# usb_keyboard.net
KiCad netlist of a schematic drawn in Altium Designer
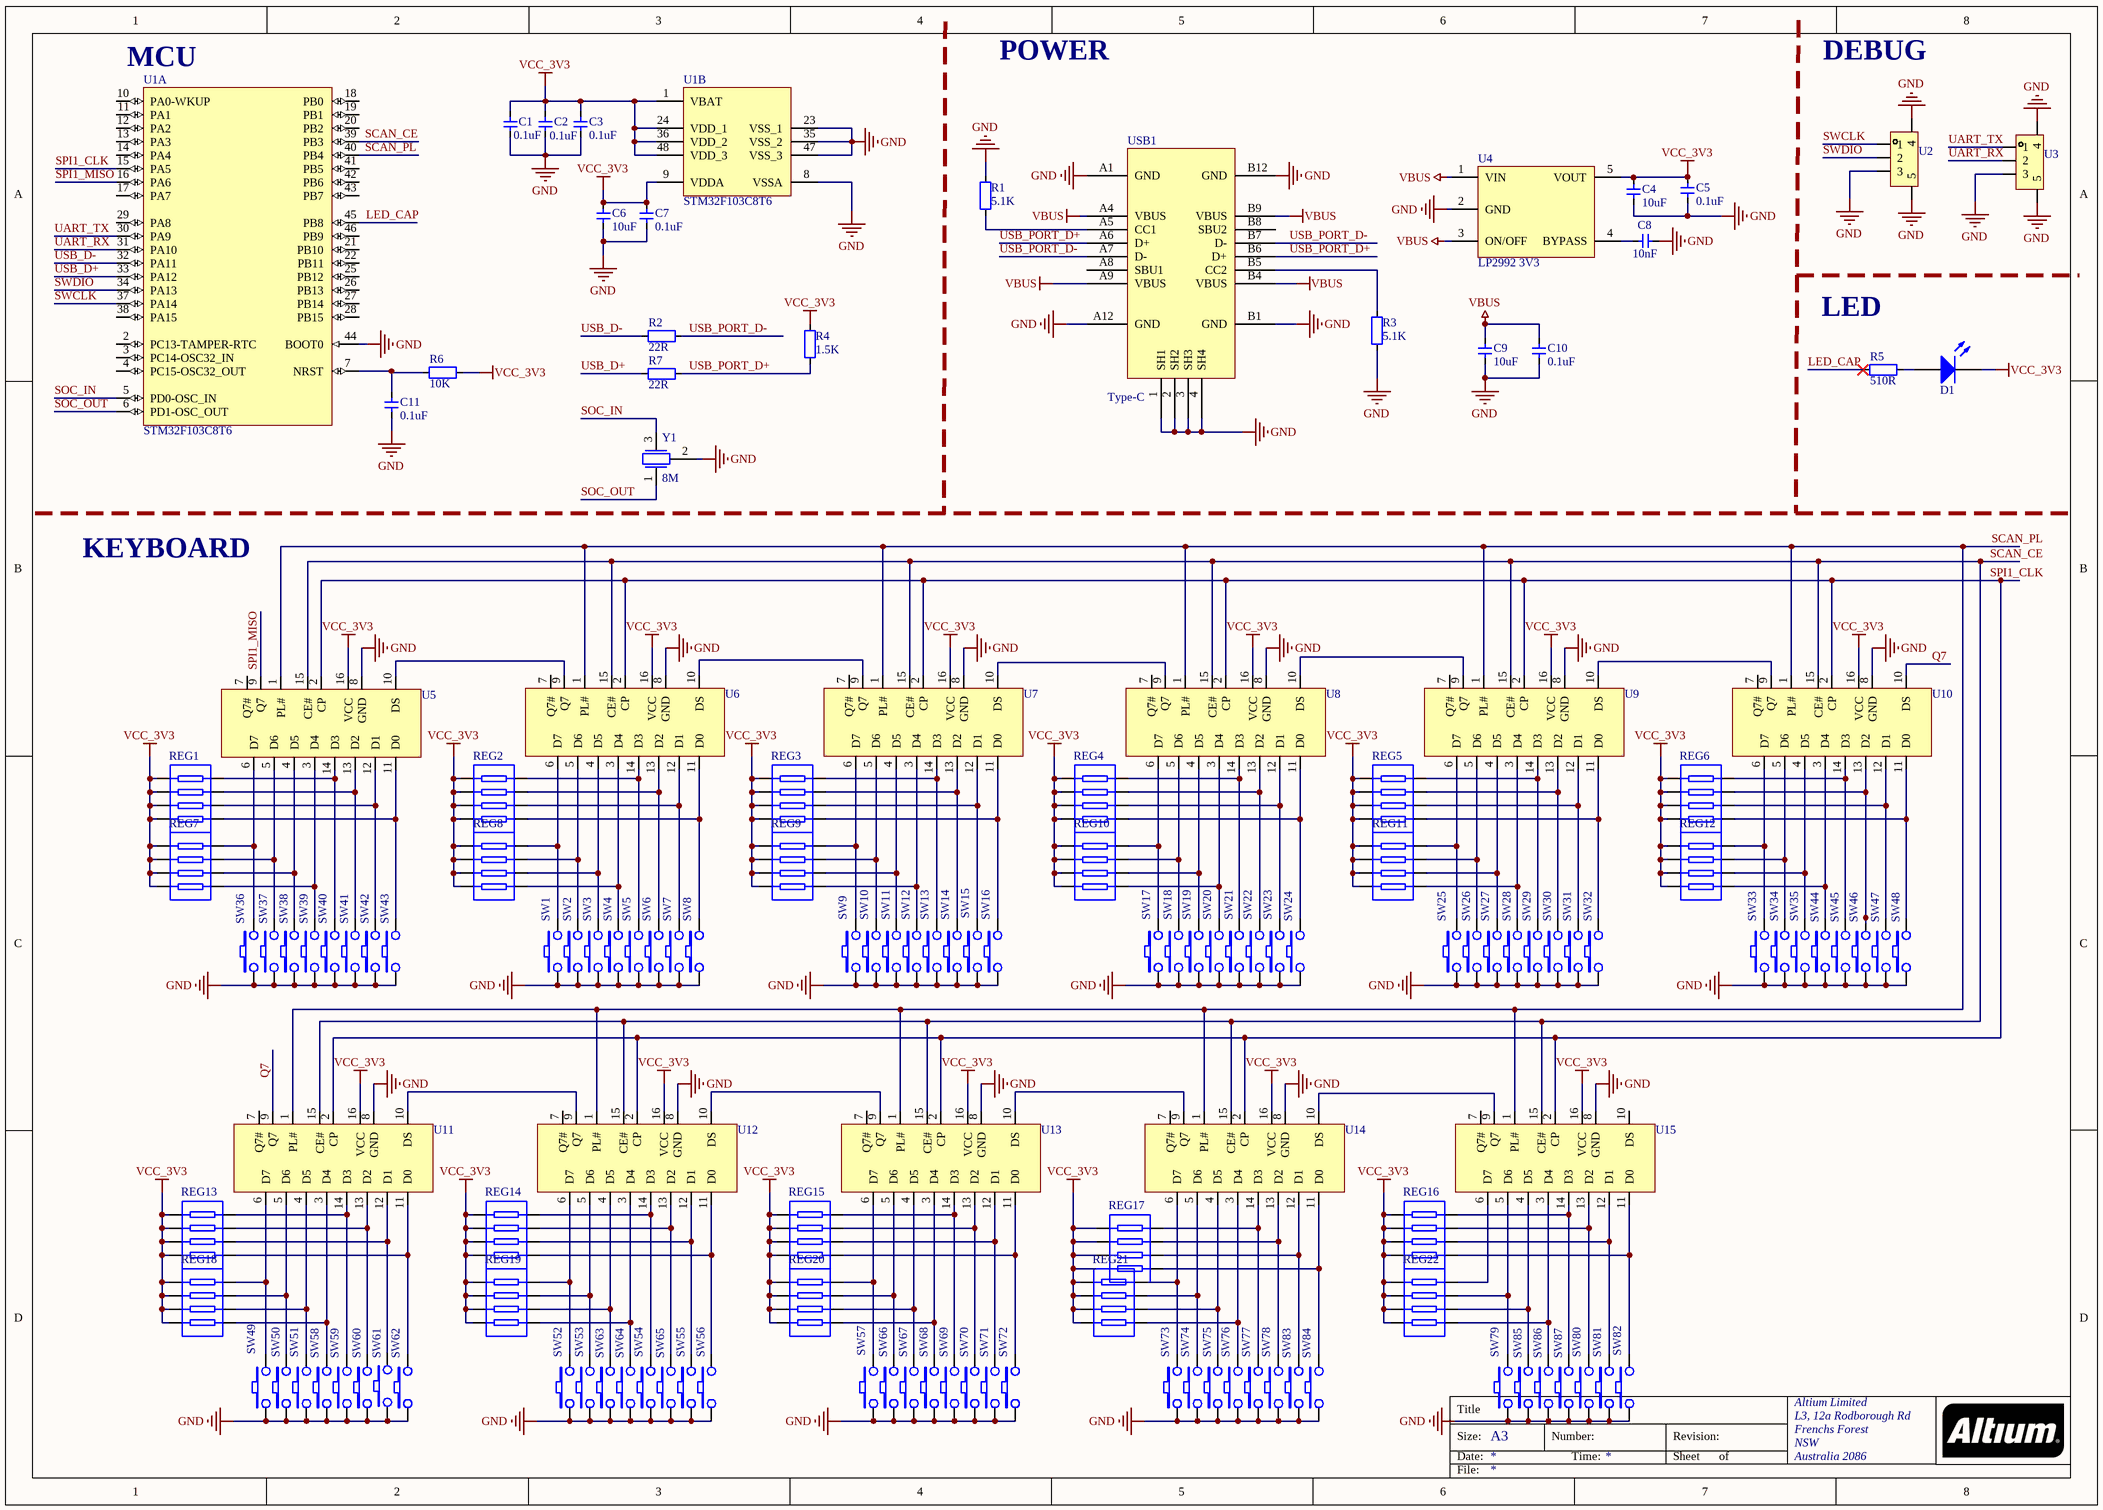
[diagram p0: usb_keyboard.SchDoc]

(export (version "E")
  (design (tool "Eeschema 10.0.6"))
  (components
    (comp (ref "C1")
      (value "0.1uF")
      (footprint "CAP_0603")
      (description "Capacitor")
      (libsource (lib "Integrated_Library") (part "电容"))
    )
    (comp (ref "C2")
      (value "0.1uF")
      (footprint "CAP_0603")
      (description "Capacitor")
      (libsource (lib "Integrated_Library") (part "电容"))
    )
    (comp (ref "C3")
      (value "0.1uF")
      (footprint "CAP_0603")
      (description "Capacitor")
      (libsource (lib "Integrated_Library") (part "电容"))
    )
    (comp (ref "C4")
      (value "10uF")
      (footprint "CAP_0603")
      (description "Capacitor")
      (libsource (lib "Integrated_Library") (part "电容"))
    )
    (comp (ref "C5")
      (value "0.1uF")
      (footprint "CAP_0603")
      (description "Capacitor")
      (libsource (lib "Integrated_Library") (part "电容"))
    )
    (comp (ref "C6")
      (value "10uF")
      (footprint "CAP_0603")
      (description "Capacitor")
      (libsource (lib "Integrated_Library") (part "电容"))
    )
    (comp (ref "C7")
      (value "0.1uF")
      (footprint "CAP_0603")
      (description "Capacitor")
      (libsource (lib "Integrated_Library") (part "电容"))
    )
    (comp (ref "C8")
      (value "10nF")
      (footprint "CAP_0603")
      (description "Capacitor")
      (libsource (lib "Integrated_Library") (part "电容"))
    )
    (comp (ref "C9")
      (value "10uF")
      (footprint "CAP_0603")
      (description "Capacitor")
      (libsource (lib "Integrated_Library") (part "电容"))
    )
    (comp (ref "C10")
      (value "0.1uF")
      (footprint "CAP_0603")
      (description "Capacitor")
      (libsource (lib "Integrated_Library") (part "电容"))
    )
    (comp (ref "C11")
      (value "0.1uF")
      (footprint "CAP_0603")
      (description "Capacitor")
      (libsource (lib "Integrated_Library") (part "电容"))
    )
    (comp (ref "D1")
      (value "LED")
      (footprint "LED_0603")
      (description "Typical INFRARED GaAs LED")
      (fields (field (name "PUBLISHER") "Altium Limited"))
      (libsource (lib "Integrated_Library") (part "LED"))
    )
    (comp (ref "R1")
      (value "5.1K")
      (footprint "REG_0603")
      (description "Resistor")
      (libsource (lib "") (part "电阻_1"))
    )
    (comp (ref "R2")
      (value "22R")
      (footprint "REG_0603")
      (description "Resistor")
      (libsource (lib "Integrated_Library") (part "电阻"))
    )
    (comp (ref "R3")
      (value "5.1K")
      (footprint "REG_0603")
      (description "Resistor")
      (libsource (lib "") (part "电阻_1"))
    )
    (comp (ref "R4")
      (value "1.5K")
      (footprint "REG_0603")
      (description "Resistor")
      (libsource (lib "") (part "电阻_1"))
    )
    (comp (ref "R5")
      (value "510R")
      (footprint "REG_0603")
      (description "Resistor")
      (libsource (lib "Integrated_Library") (part "电阻"))
    )
    (comp (ref "R6")
      (value "10K")
      (footprint "REG_0603")
      (description "Resistor")
      (libsource (lib "Integrated_Library") (part "电阻"))
    )
    (comp (ref "R7")
      (value "22R")
      (footprint "REG_0603")
      (description "Resistor")
      (libsource (lib "Integrated_Library") (part "电阻"))
    )
    (comp (ref "REG1")
      (value "4D03WGJ0103T5E")
      (footprint "RES-ARRAY-SMD_0603-8P-L3.2-W1.6-BL")
      (description "阻值:10kΩ;精度:±5%;单个元件功率:62.5mW;温度系数:±200ppm/;电阻器数:4;引脚数:8;")
      (fields (field (name "MANUFACTURER") "UNI-ROYAL(厚声)") (field (name "TOLERANCE") "±5%"))
      (libsource (lib "Integrated_Library") (part "排阻"))
    )
    (comp (ref "REG2")
      (value "4D03WGJ0103T5E")
      (footprint "RES-ARRAY-SMD_0603-8P-L3.2-W1.6-BL")
      (description "阻值:10kΩ;精度:±5%;单个元件功率:62.5mW;温度系数:±200ppm/;电阻器数:4;引脚数:8;")
      (fields (field (name "MANUFACTURER") "UNI-ROYAL(厚声)") (field (name "TOLERANCE") "±5%"))
      (libsource (lib "Integrated_Library") (part "排阻"))
    )
    (comp (ref "REG3")
      (value "4D03WGJ0103T5E")
      (footprint "RES-ARRAY-SMD_0603-8P-L3.2-W1.6-BL")
      (description "阻值:10kΩ;精度:±5%;单个元件功率:62.5mW;温度系数:±200ppm/;电阻器数:4;引脚数:8;")
      (fields (field (name "MANUFACTURER") "UNI-ROYAL(厚声)") (field (name "TOLERANCE") "±5%"))
      (libsource (lib "Integrated_Library") (part "排阻"))
    )
    (comp (ref "REG4")
      (value "4D03WGJ0103T5E")
      (footprint "RES-ARRAY-SMD_0603-8P-L3.2-W1.6-BL")
      (description "阻值:10kΩ;精度:±5%;单个元件功率:62.5mW;温度系数:±200ppm/;电阻器数:4;引脚数:8;")
      (fields (field (name "MANUFACTURER") "UNI-ROYAL(厚声)") (field (name "TOLERANCE") "±5%"))
      (libsource (lib "Integrated_Library") (part "排阻"))
    )
    (comp (ref "REG5")
      (value "4D03WGJ0103T5E")
      (footprint "RES-ARRAY-SMD_0603-8P-L3.2-W1.6-BL")
      (description "阻值:10kΩ;精度:±5%;单个元件功率:62.5mW;温度系数:±200ppm/;电阻器数:4;引脚数:8;")
      (fields (field (name "MANUFACTURER") "UNI-ROYAL(厚声)") (field (name "TOLERANCE") "±5%"))
      (libsource (lib "Integrated_Library") (part "排阻"))
    )
    (comp (ref "REG6")
      (value "4D03WGJ0103T5E")
      (footprint "RES-ARRAY-SMD_0603-8P-L3.2-W1.6-BL")
      (description "阻值:10kΩ;精度:±5%;单个元件功率:62.5mW;温度系数:±200ppm/;电阻器数:4;引脚数:8;")
      (fields (field (name "MANUFACTURER") "UNI-ROYAL(厚声)") (field (name "TOLERANCE") "±5%"))
      (libsource (lib "Integrated_Library") (part "排阻"))
    )
    (comp (ref "REG7")
      (value "4D03WGJ0103T5E")
      (footprint "RES-ARRAY-SMD_0603-8P-L3.2-W1.6-BL")
      (description "阻值:10kΩ;精度:±5%;单个元件功率:62.5mW;温度系数:±200ppm/;电阻器数:4;引脚数:8;")
      (fields (field (name "MANUFACTURER") "UNI-ROYAL(厚声)") (field (name "TOLERANCE") "±5%"))
      (libsource (lib "Integrated_Library") (part "排阻"))
    )
    (comp (ref "REG8")
      (value "4D03WGJ0103T5E")
      (footprint "RES-ARRAY-SMD_0603-8P-L3.2-W1.6-BL")
      (description "阻值:10kΩ;精度:±5%;单个元件功率:62.5mW;温度系数:±200ppm/;电阻器数:4;引脚数:8;")
      (fields (field (name "MANUFACTURER") "UNI-ROYAL(厚声)") (field (name "TOLERANCE") "±5%"))
      (libsource (lib "Integrated_Library") (part "排阻"))
    )
    (comp (ref "REG9")
      (value "4D03WGJ0103T5E")
      (footprint "RES-ARRAY-SMD_0603-8P-L3.2-W1.6-BL")
      (description "阻值:10kΩ;精度:±5%;单个元件功率:62.5mW;温度系数:±200ppm/;电阻器数:4;引脚数:8;")
      (fields (field (name "MANUFACTURER") "UNI-ROYAL(厚声)") (field (name "TOLERANCE") "±5%"))
      (libsource (lib "Integrated_Library") (part "排阻"))
    )
    (comp (ref "REG10")
      (value "4D03WGJ0103T5E")
      (footprint "RES-ARRAY-SMD_0603-8P-L3.2-W1.6-BL")
      (description "阻值:10kΩ;精度:±5%;单个元件功率:62.5mW;温度系数:±200ppm/;电阻器数:4;引脚数:8;")
      (fields (field (name "MANUFACTURER") "UNI-ROYAL(厚声)") (field (name "TOLERANCE") "±5%"))
      (libsource (lib "Integrated_Library") (part "排阻"))
    )
    (comp (ref "REG11")
      (value "4D03WGJ0103T5E")
      (footprint "RES-ARRAY-SMD_0603-8P-L3.2-W1.6-BL")
      (description "阻值:10kΩ;精度:±5%;单个元件功率:62.5mW;温度系数:±200ppm/;电阻器数:4;引脚数:8;")
      (fields (field (name "MANUFACTURER") "UNI-ROYAL(厚声)") (field (name "TOLERANCE") "±5%"))
      (libsource (lib "Integrated_Library") (part "排阻"))
    )
    (comp (ref "REG12")
      (value "4D03WGJ0103T5E")
      (footprint "RES-ARRAY-SMD_0603-8P-L3.2-W1.6-BL")
      (description "阻值:10kΩ;精度:±5%;单个元件功率:62.5mW;温度系数:±200ppm/;电阻器数:4;引脚数:8;")
      (fields (field (name "MANUFACTURER") "UNI-ROYAL(厚声)") (field (name "TOLERANCE") "±5%"))
      (libsource (lib "Integrated_Library") (part "排阻"))
    )
    (comp (ref "REG13")
      (value "4D03WGJ0103T5E")
      (footprint "RES-ARRAY-SMD_0603-8P-L3.2-W1.6-BL")
      (description "阻值:10kΩ;精度:±5%;单个元件功率:62.5mW;温度系数:±200ppm/;电阻器数:4;引脚数:8;")
      (fields (field (name "MANUFACTURER") "UNI-ROYAL(厚声)") (field (name "TOLERANCE") "±5%"))
      (libsource (lib "Integrated_Library") (part "排阻"))
    )
    (comp (ref "REG14")
      (value "4D03WGJ0103T5E")
      (footprint "RES-ARRAY-SMD_0603-8P-L3.2-W1.6-BL")
      (description "阻值:10kΩ;精度:±5%;单个元件功率:62.5mW;温度系数:±200ppm/;电阻器数:4;引脚数:8;")
      (fields (field (name "MANUFACTURER") "UNI-ROYAL(厚声)") (field (name "TOLERANCE") "±5%"))
      (libsource (lib "Integrated_Library") (part "排阻"))
    )
    (comp (ref "REG15")
      (value "4D03WGJ0103T5E")
      (footprint "RES-ARRAY-SMD_0603-8P-L3.2-W1.6-BL")
      (description "阻值:10kΩ;精度:±5%;单个元件功率:62.5mW;温度系数:±200ppm/;电阻器数:4;引脚数:8;")
      (fields (field (name "MANUFACTURER") "UNI-ROYAL(厚声)") (field (name "TOLERANCE") "±5%"))
      (libsource (lib "Integrated_Library") (part "排阻"))
    )
    (comp (ref "REG16")
      (value "4D03WGJ0103T5E")
      (footprint "RES-ARRAY-SMD_0603-8P-L3.2-W1.6-BL")
      (description "阻值:10kΩ;精度:±5%;单个元件功率:62.5mW;温度系数:±200ppm/;电阻器数:4;引脚数:8;")
      (fields (field (name "MANUFACTURER") "UNI-ROYAL(厚声)") (field (name "TOLERANCE") "±5%"))
      (libsource (lib "Integrated_Library") (part "排阻"))
    )
    (comp (ref "REG17")
      (value "4D03WGJ0103T5E")
      (footprint "RES-ARRAY-SMD_0603-8P-L3.2-W1.6-BL")
      (description "阻值:10kΩ;精度:±5%;单个元件功率:62.5mW;温度系数:±200ppm/;电阻器数:4;引脚数:8;")
      (fields (field (name "MANUFACTURER") "UNI-ROYAL(厚声)") (field (name "TOLERANCE") "±5%"))
      (libsource (lib "Integrated_Library") (part "排阻"))
    )
    (comp (ref "REG18")
      (value "4D03WGJ0103T5E")
      (footprint "RES-ARRAY-SMD_0603-8P-L3.2-W1.6-BL")
      (description "阻值:10kΩ;精度:±5%;单个元件功率:62.5mW;温度系数:±200ppm/;电阻器数:4;引脚数:8;")
      (fields (field (name "MANUFACTURER") "UNI-ROYAL(厚声)") (field (name "TOLERANCE") "±5%"))
      (libsource (lib "Integrated_Library") (part "排阻"))
    )
    (comp (ref "REG19")
      (value "4D03WGJ0103T5E")
      (footprint "RES-ARRAY-SMD_0603-8P-L3.2-W1.6-BL")
      (description "阻值:10kΩ;精度:±5%;单个元件功率:62.5mW;温度系数:±200ppm/;电阻器数:4;引脚数:8;")
      (fields (field (name "MANUFACTURER") "UNI-ROYAL(厚声)") (field (name "TOLERANCE") "±5%"))
      (libsource (lib "Integrated_Library") (part "排阻"))
    )
    (comp (ref "REG20")
      (value "4D03WGJ0103T5E")
      (footprint "RES-ARRAY-SMD_0603-8P-L3.2-W1.6-BL")
      (description "阻值:10kΩ;精度:±5%;单个元件功率:62.5mW;温度系数:±200ppm/;电阻器数:4;引脚数:8;")
      (fields (field (name "MANUFACTURER") "UNI-ROYAL(厚声)") (field (name "TOLERANCE") "±5%"))
      (libsource (lib "Integrated_Library") (part "排阻"))
    )
    (comp (ref "REG21")
      (value "4D03WGJ0103T5E")
      (footprint "RES-ARRAY-SMD_0603-8P-L3.2-W1.6-BL")
      (description "阻值:10kΩ;精度:±5%;单个元件功率:62.5mW;温度系数:±200ppm/;电阻器数:4;引脚数:8;")
      (fields (field (name "MANUFACTURER") "UNI-ROYAL(厚声)") (field (name "TOLERANCE") "±5%"))
      (libsource (lib "Integrated_Library") (part "排阻"))
    )
    (comp (ref "REG22")
      (value "4D03WGJ0103T5E")
      (footprint "RES-ARRAY-SMD_0603-8P-L3.2-W1.6-BL")
      (description "阻值:10kΩ;精度:±5%;单个元件功率:62.5mW;温度系数:±200ppm/;电阻器数:4;引脚数:8;")
      (fields (field (name "MANUFACTURER") "UNI-ROYAL(厚声)") (field (name "TOLERANCE") "±5%"))
      (libsource (lib "Integrated_Library") (part "排阻"))
    )
    (comp (ref "SW1")
      (value "SW")
      (footprint "KEY_Mechanical")
      (libsource (lib "Integrated_Library") (part "SW"))
    )
    (comp (ref "SW2")
      (value "SW")
      (footprint "KEY_Mechanical")
      (libsource (lib "Integrated_Library") (part "SW"))
    )
    (comp (ref "SW3")
      (value "SW")
      (footprint "KEY_Mechanical")
      (libsource (lib "Integrated_Library") (part "SW"))
    )
    (comp (ref "SW4")
      (value "SW")
      (footprint "KEY_Mechanical")
      (libsource (lib "Integrated_Library") (part "SW"))
    )
    (comp (ref "SW5")
      (value "SW")
      (footprint "KEY_Mechanical")
      (libsource (lib "Integrated_Library") (part "SW"))
    )
    (comp (ref "SW6")
      (value "SW")
      (footprint "KEY_Mechanical")
      (libsource (lib "Integrated_Library") (part "SW"))
    )
    (comp (ref "SW7")
      (value "SW")
      (footprint "KEY_Mechanical")
      (libsource (lib "Integrated_Library") (part "SW"))
    )
    (comp (ref "SW8")
      (value "SW")
      (footprint "KEY_Mechanical")
      (libsource (lib "Integrated_Library") (part "SW"))
    )
    (comp (ref "SW9")
      (value "SW")
      (footprint "KEY_Mechanical")
      (libsource (lib "Integrated_Library") (part "SW"))
    )
    (comp (ref "SW10")
      (value "SW")
      (footprint "KEY_Mechanical")
      (libsource (lib "Integrated_Library") (part "SW"))
    )
    (comp (ref "SW11")
      (value "SW")
      (footprint "KEY_Mechanical")
      (libsource (lib "Integrated_Library") (part "SW"))
    )
    (comp (ref "SW12")
      (value "SW")
      (footprint "KEY_Mechanical")
      (libsource (lib "Integrated_Library") (part "SW"))
    )
    (comp (ref "SW13")
      (value "SW")
      (footprint "KEY_Mechanical")
      (libsource (lib "Integrated_Library") (part "SW"))
    )
    (comp (ref "SW14")
      (value "SW")
      (footprint "KEY_Mechanical")
      (libsource (lib "Integrated_Library") (part "SW"))
    )
    (comp (ref "SW15")
      (value "SW")
      (footprint "KEY_Mechanical")
      (libsource (lib "Integrated_Library") (part "SW"))
    )
    (comp (ref "SW16")
      (value "SW")
      (footprint "KEY_Mechanical")
      (libsource (lib "Integrated_Library") (part "SW"))
    )
    (comp (ref "SW17")
      (value "SW")
      (footprint "KEY_Mechanical")
      (libsource (lib "Integrated_Library") (part "SW"))
    )
    (comp (ref "SW18")
      (value "SW")
      (footprint "KEY_Mechanical")
      (libsource (lib "Integrated_Library") (part "SW"))
    )
    (comp (ref "SW19")
      (value "SW")
      (footprint "KEY_Mechanical")
      (libsource (lib "Integrated_Library") (part "SW"))
    )
    (comp (ref "SW20")
      (value "SW")
      (footprint "KEY_Mechanical")
      (libsource (lib "Integrated_Library") (part "SW"))
    )
    (comp (ref "SW21")
      (value "SW")
      (footprint "KEY_Mechanical")
      (libsource (lib "Integrated_Library") (part "SW"))
    )
    (comp (ref "SW22")
      (value "SW")
      (footprint "KEY_Mechanical")
      (libsource (lib "Integrated_Library") (part "SW"))
    )
    (comp (ref "SW23")
      (value "SW")
      (footprint "KEY_Mechanical")
      (libsource (lib "Integrated_Library") (part "SW"))
    )
    (comp (ref "SW24")
      (value "SW")
      (footprint "KEY_Mechanical")
      (libsource (lib "Integrated_Library") (part "SW"))
    )
    (comp (ref "SW25")
      (value "SW")
      (footprint "KEY_Mechanical")
      (libsource (lib "Integrated_Library") (part "SW"))
    )
    (comp (ref "SW26")
      (value "SW")
      (footprint "KEY_Mechanical")
      (libsource (lib "Integrated_Library") (part "SW"))
    )
    (comp (ref "SW27")
      (value "SW")
      (footprint "KEY_Mechanical")
      (libsource (lib "Integrated_Library") (part "SW"))
    )
    (comp (ref "SW28")
      (value "SW")
      (footprint "KEY_Mechanical")
      (libsource (lib "Integrated_Library") (part "SW"))
    )
    (comp (ref "SW29")
      (value "SW")
      (footprint "KEY_Mechanical")
      (libsource (lib "Integrated_Library") (part "SW"))
    )
    (comp (ref "SW30")
      (value "SW")
      (footprint "KEY_Mechanical")
      (libsource (lib "Integrated_Library") (part "SW"))
    )
    (comp (ref "SW31")
      (value "SW")
      (footprint "KEY_Mechanical")
      (libsource (lib "Integrated_Library") (part "SW"))
    )
    (comp (ref "SW32")
      (value "SW")
      (footprint "KEY_Mechanical")
      (libsource (lib "Integrated_Library") (part "SW"))
    )
    (comp (ref "SW33")
      (value "SW")
      (footprint "KEY_Mechanical")
      (libsource (lib "Integrated_Library") (part "SW"))
    )
    (comp (ref "SW34")
      (value "SW")
      (footprint "KEY_Mechanical")
      (libsource (lib "Integrated_Library") (part "SW"))
    )
    (comp (ref "SW35")
      (value "SW")
      (footprint "KEY_Mechanical")
      (libsource (lib "Integrated_Library") (part "SW"))
    )
    (comp (ref "SW36")
      (value "SW")
      (footprint "KEY_Mechanical")
      (libsource (lib "Integrated_Library") (part "SW"))
    )
    (comp (ref "SW37")
      (value "SW")
      (footprint "KEY_Mechanical")
      (libsource (lib "Integrated_Library") (part "SW"))
    )
    (comp (ref "SW38")
      (value "SW")
      (footprint "KEY_Mechanical")
      (libsource (lib "Integrated_Library") (part "SW"))
    )
    (comp (ref "SW39")
      (value "SW")
      (footprint "KEY_Mechanical")
      (libsource (lib "Integrated_Library") (part "SW"))
    )
    (comp (ref "SW40")
      (value "SW")
      (footprint "KEY_Mechanical")
      (libsource (lib "Integrated_Library") (part "SW"))
    )
    (comp (ref "SW41")
      (value "SW")
      (footprint "KEY_Mechanical")
      (libsource (lib "Integrated_Library") (part "SW"))
    )
    (comp (ref "SW42")
      (value "SW")
      (footprint "KEY_Mechanical")
      (libsource (lib "Integrated_Library") (part "SW"))
    )
    (comp (ref "SW43")
      (value "SW")
      (footprint "KEY_Mechanical")
      (libsource (lib "Integrated_Library") (part "SW"))
    )
    (comp (ref "SW44")
      (value "SW")
      (footprint "KEY_Mechanical")
      (libsource (lib "Integrated_Library") (part "SW"))
    )
    (comp (ref "SW45")
      (value "SW")
      (footprint "KEY_Mechanical")
      (libsource (lib "Integrated_Library") (part "SW"))
    )
    (comp (ref "SW46")
      (value "SW")
      (footprint "KEY_Mechanical")
      (libsource (lib "Integrated_Library") (part "SW"))
    )
    (comp (ref "SW47")
      (value "SW")
      (footprint "KEY_Mechanical")
      (libsource (lib "Integrated_Library") (part "SW"))
    )
    (comp (ref "SW48")
      (value "SW")
      (footprint "KEY_Mechanical")
      (libsource (lib "Integrated_Library") (part "SW"))
    )
    (comp (ref "SW49")
      (value "SW")
      (footprint "KEY_Mechanical")
      (libsource (lib "Integrated_Library") (part "SW"))
    )
    (comp (ref "SW50")
      (value "SW")
      (footprint "KEY_Mechanical")
      (libsource (lib "Integrated_Library") (part "SW"))
    )
    (comp (ref "SW51")
      (value "SW")
      (footprint "KEY_Mechanical")
      (libsource (lib "Integrated_Library") (part "SW"))
    )
    (comp (ref "SW52")
      (value "SW")
      (footprint "KEY_Mechanical")
      (libsource (lib "Integrated_Library") (part "SW"))
    )
    (comp (ref "SW53")
      (value "SW")
      (footprint "KEY_Mechanical")
      (libsource (lib "Integrated_Library") (part "SW"))
    )
    (comp (ref "SW54")
      (value "SW")
      (footprint "KEY_Mechanical")
      (libsource (lib "Integrated_Library") (part "SW"))
    )
    (comp (ref "SW55")
      (value "SW")
      (footprint "KEY_Mechanical")
      (libsource (lib "Integrated_Library") (part "SW"))
    )
    (comp (ref "SW56")
      (value "SW")
      (footprint "KEY_Mechanical")
      (libsource (lib "Integrated_Library") (part "SW"))
    )
    (comp (ref "SW57")
      (value "SW")
      (footprint "KEY_Mechanical")
      (libsource (lib "Integrated_Library") (part "SW"))
    )
    (comp (ref "SW58")
      (value "SW")
      (footprint "KEY_Mechanical")
      (libsource (lib "Integrated_Library") (part "SW"))
    )
    (comp (ref "SW59")
      (value "SW")
      (footprint "KEY_Mechanical")
      (libsource (lib "Integrated_Library") (part "SW"))
    )
    (comp (ref "SW60")
      (value "SW")
      (footprint "KEY_Mechanical")
      (libsource (lib "Integrated_Library") (part "SW"))
    )
    (comp (ref "SW61")
      (value "SW")
      (footprint "KEY_Mechanical")
      (libsource (lib "Integrated_Library") (part "SW"))
    )
    (comp (ref "SW62")
      (value "SW")
      (footprint "KEY_Mechanical")
      (libsource (lib "Integrated_Library") (part "SW"))
    )
    (comp (ref "SW63")
      (value "SW")
      (footprint "KEY_Mechanical")
      (libsource (lib "Integrated_Library") (part "SW"))
    )
    (comp (ref "SW64")
      (value "SW")
      (footprint "KEY_Mechanical")
      (libsource (lib "Integrated_Library") (part "SW"))
    )
    (comp (ref "SW65")
      (value "SW")
      (footprint "KEY_Mechanical")
      (libsource (lib "Integrated_Library") (part "SW"))
    )
    (comp (ref "SW66")
      (value "SW")
      (footprint "KEY_Mechanical")
      (libsource (lib "Integrated_Library") (part "SW"))
    )
    (comp (ref "SW67")
      (value "SW")
      (footprint "KEY_Mechanical")
      (libsource (lib "Integrated_Library") (part "SW"))
    )
    (comp (ref "SW68")
      (value "SW")
      (footprint "KEY_Mechanical")
      (libsource (lib "Integrated_Library") (part "SW"))
    )
    (comp (ref "SW69")
      (value "SW")
      (footprint "KEY_Mechanical")
      (libsource (lib "Integrated_Library") (part "SW"))
    )
    (comp (ref "SW70")
      (value "SW")
      (footprint "KEY_Mechanical")
      (libsource (lib "Integrated_Library") (part "SW"))
    )
    (comp (ref "SW71")
      (value "SW")
      (footprint "KEY_Mechanical")
      (libsource (lib "Integrated_Library") (part "SW"))
    )
    (comp (ref "SW72")
      (value "SW")
      (footprint "KEY_Mechanical")
      (libsource (lib "Integrated_Library") (part "SW"))
    )
    (comp (ref "SW73")
      (value "SW")
      (footprint "KEY_Mechanical")
      (libsource (lib "Integrated_Library") (part "SW"))
    )
    (comp (ref "SW74")
      (value "SW")
      (footprint "KEY_Mechanical")
      (libsource (lib "Integrated_Library") (part "SW"))
    )
    (comp (ref "SW75")
      (value "SW")
      (footprint "KEY_Mechanical")
      (libsource (lib "Integrated_Library") (part "SW"))
    )
    (comp (ref "SW76")
      (value "SW")
      (footprint "KEY_Mechanical")
      (libsource (lib "Integrated_Library") (part "SW"))
    )
    (comp (ref "SW77")
      (value "SW")
      (footprint "KEY_Mechanical")
      (libsource (lib "Integrated_Library") (part "SW"))
    )
    (comp (ref "SW78")
      (value "SW")
      (footprint "KEY_Mechanical")
      (libsource (lib "Integrated_Library") (part "SW"))
    )
    (comp (ref "SW79")
      (value "SW")
      (footprint "KEY_Mechanical")
      (libsource (lib "Integrated_Library") (part "SW"))
    )
    (comp (ref "SW80")
      (value "SW")
      (footprint "KEY_Mechanical")
      (libsource (lib "Integrated_Library") (part "SW"))
    )
    (comp (ref "SW81")
      (value "SW")
      (footprint "KEY_Mechanical")
      (libsource (lib "Integrated_Library") (part "SW"))
    )
    (comp (ref "SW82")
      (value "SW")
      (footprint "KEY_Mechanical")
      (libsource (lib "Integrated_Library") (part "SW"))
    )
    (comp (ref "SW83")
      (value "SW")
      (footprint "KEY_Mechanical")
      (libsource (lib "Integrated_Library") (part "SW"))
    )
    (comp (ref "SW84")
      (value "SW")
      (footprint "KEY_Mechanical")
      (libsource (lib "Integrated_Library") (part "SW"))
    )
    (comp (ref "SW85")
      (value "SW")
      (footprint "KEY_Mechanical")
      (libsource (lib "Integrated_Library") (part "SW"))
    )
    (comp (ref "SW86")
      (value "SW")
      (footprint "KEY_Mechanical")
      (libsource (lib "Integrated_Library") (part "SW"))
    )
    (comp (ref "SW87")
      (value "SW")
      (footprint "KEY_Mechanical")
      (libsource (lib "Integrated_Library") (part "SW"))
    )
    (comp (ref "U1")
      (value "STM32F103C8T6")
      (footprint "STM-LQFP48_L")
      (libsource (lib "STMicroelectronics STM32 F1") (part "STM32F103C8T6"))
    )
    (comp (ref "U2")
      (value "SH1.0-3P-STAND")
      (footprint "SH1.0-3P-STAND")
      (libsource (lib "Integrated_Library") (part "SH1.0-3P-STAND"))
    )
    (comp (ref "U3")
      (value "SH1.0-3P-STAND")
      (footprint "SH1.0-3P-STAND")
      (libsource (lib "Integrated_Library") (part "SH1.0-3P-STAND"))
    )
    (comp (ref "U4")
      (value "LP2992 3V3")
      (footprint "SOT23-5")
      (description "LDO")
      (libsource (lib "Integrated_Library") (part "LP2992"))
    )
    (comp (ref "U5")
      (value "74HC165D,653")
      (footprint "SOIC-16_L9.9-W3.9-P1.27-LS6.0-BL")
      (fields (field (name "MANUFACTURER") "Nexperia(安世)"))
      (libsource (lib "Integrated_Library") (part "74HC165D,653"))
    )
    (comp (ref "U6")
      (value "74HC165D,653")
      (footprint "SOIC-16_L9.9-W3.9-P1.27-LS6.0-BL")
      (fields (field (name "MANUFACTURER") "Nexperia(安世)"))
      (libsource (lib "Integrated_Library") (part "74HC165D,653"))
    )
    (comp (ref "U7")
      (value "74HC165D,653")
      (footprint "SOIC-16_L9.9-W3.9-P1.27-LS6.0-BL")
      (fields (field (name "MANUFACTURER") "Nexperia(安世)"))
      (libsource (lib "Integrated_Library") (part "74HC165D,653"))
    )
    (comp (ref "U8")
      (value "74HC165D,653")
      (footprint "SOIC-16_L9.9-W3.9-P1.27-LS6.0-BL")
      (fields (field (name "MANUFACTURER") "Nexperia(安世)"))
      (libsource (lib "Integrated_Library") (part "74HC165D,653"))
    )
    (comp (ref "U9")
      (value "74HC165D,653")
      (footprint "SOIC-16_L9.9-W3.9-P1.27-LS6.0-BL")
      (fields (field (name "MANUFACTURER") "Nexperia(安世)"))
      (libsource (lib "Integrated_Library") (part "74HC165D,653"))
    )
    (comp (ref "U10")
      (value "74HC165D,653")
      (footprint "SOIC-16_L9.9-W3.9-P1.27-LS6.0-BL")
      (fields (field (name "MANUFACTURER") "Nexperia(安世)"))
      (libsource (lib "Integrated_Library") (part "74HC165D,653"))
    )
    (comp (ref "U11")
      (value "74HC165D,653")
      (footprint "SOIC-16_L9.9-W3.9-P1.27-LS6.0-BL")
      (fields (field (name "MANUFACTURER") "Nexperia(安世)"))
      (libsource (lib "Integrated_Library") (part "74HC165D,653"))
    )
    (comp (ref "U12")
      (value "74HC165D,653")
      (footprint "SOIC-16_L9.9-W3.9-P1.27-LS6.0-BL")
      (fields (field (name "MANUFACTURER") "Nexperia(安世)"))
      (libsource (lib "Integrated_Library") (part "74HC165D,653"))
    )
    (comp (ref "U13")
      (value "74HC165D,653")
      (footprint "SOIC-16_L9.9-W3.9-P1.27-LS6.0-BL")
      (fields (field (name "MANUFACTURER") "Nexperia(安世)"))
      (libsource (lib "Integrated_Library") (part "74HC165D,653"))
    )
    (comp (ref "U14")
      (value "74HC165D,653")
      (footprint "SOIC-16_L9.9-W3.9-P1.27-LS6.0-BL")
      (fields (field (name "MANUFACTURER") "Nexperia(安世)"))
      (libsource (lib "Integrated_Library") (part "74HC165D,653"))
    )
    (comp (ref "U15")
      (value "74HC165D,653")
      (footprint "SOIC-16_L9.9-W3.9-P1.27-LS6.0-BL")
      (fields (field (name "MANUFACTURER") "Nexperia(安世)"))
      (libsource (lib "Integrated_Library") (part "74HC165D,653"))
    )
    (comp (ref "USB1")
      (value "Type-C")
      (footprint "Type-C-TOP")
      (libsource (lib "Integrated_Library") (part "USB-Type-C-TOP"))
    )
    (comp (ref "Y1")
      (value "8M")
      (footprint "晶振-3P")
      (description "村田贴片")
      (libsource (lib "Integrated_Library") (part "晶振-3Pin"))
    )
  )
  (nets
    (net (code "1") (name "/LED_CAP") (class "Default")
      (node (ref "R5") (pin "1") (pinfunction "1_1") (pintype "passive"))
      (node (ref "U1") (pin "45") (pinfunction "PB8_45") (pintype "bidirectional"))
    )
    (net (code "2") (name "/Q7") (class "Default")
      (node (ref "U10") (pin "10") (pinfunction "DS_10") (pintype "passive"))
      (node (ref "U11") (pin "9") (pinfunction "Q7_9") (pintype "passive"))
    )
    (net (code "3") (name "/SCAN_CE") (class "Default")
      (node (ref "U1") (pin "39") (pinfunction "PB3_39") (pintype "bidirectional"))
      (node (ref "U10") (pin "15") (pinfunction "CE#_15") (pintype "passive"))
      (node (ref "U11") (pin "15") (pinfunction "CE#_15") (pintype "passive"))
      (node (ref "U12") (pin "15") (pinfunction "CE#_15") (pintype "passive"))
      (node (ref "U13") (pin "15") (pinfunction "CE#_15") (pintype "passive"))
      (node (ref "U14") (pin "15") (pinfunction "CE#_15") (pintype "passive"))
      (node (ref "U15") (pin "15") (pinfunction "CE#_15") (pintype "passive"))
      (node (ref "U5") (pin "15") (pinfunction "CE#_15") (pintype "passive"))
      (node (ref "U6") (pin "15") (pinfunction "CE#_15") (pintype "passive"))
      (node (ref "U7") (pin "15") (pinfunction "CE#_15") (pintype "passive"))
      (node (ref "U8") (pin "15") (pinfunction "CE#_15") (pintype "passive"))
      (node (ref "U9") (pin "15") (pinfunction "CE#_15") (pintype "passive"))
    )
    (net (code "4") (name "/SCAN_PL") (class "Default")
      (node (ref "U1") (pin "40") (pinfunction "PB4_40") (pintype "bidirectional"))
      (node (ref "U10") (pin "1") (pinfunction "PL#_1") (pintype "passive"))
      (node (ref "U11") (pin "1") (pinfunction "PL#_1") (pintype "passive"))
      (node (ref "U12") (pin "1") (pinfunction "PL#_1") (pintype "passive"))
      (node (ref "U13") (pin "1") (pinfunction "PL#_1") (pintype "passive"))
      (node (ref "U14") (pin "1") (pinfunction "PL#_1") (pintype "passive"))
      (node (ref "U15") (pin "1") (pinfunction "PL#_1") (pintype "passive"))
      (node (ref "U5") (pin "1") (pinfunction "PL#_1") (pintype "passive"))
      (node (ref "U6") (pin "1") (pinfunction "PL#_1") (pintype "passive"))
      (node (ref "U7") (pin "1") (pinfunction "PL#_1") (pintype "passive"))
      (node (ref "U8") (pin "1") (pinfunction "PL#_1") (pintype "passive"))
      (node (ref "U9") (pin "1") (pinfunction "PL#_1") (pintype "passive"))
    )
    (net (code "5") (name "/SOC_IN") (class "Default")
      (node (ref "U1") (pin "5") (pinfunction "PD0-OSC_IN_5") (pintype "bidirectional"))
      (node (ref "Y1") (pin "3") (pinfunction "3_3") (pintype "passive"))
    )
    (net (code "6") (name "/SOC_OUT") (class "Default")
      (node (ref "U1") (pin "6") (pinfunction "PD1-OSC_OUT_6") (pintype "bidirectional"))
      (node (ref "Y1") (pin "1") (pinfunction "1_1") (pintype "passive"))
    )
    (net (code "7") (name "/SPI1_CLK") (class "Default")
      (node (ref "U1") (pin "15") (pinfunction "PA5_15") (pintype "bidirectional"))
      (node (ref "U10") (pin "2") (pinfunction "CP_2") (pintype "passive"))
      (node (ref "U11") (pin "2") (pinfunction "CP_2") (pintype "passive"))
      (node (ref "U12") (pin "2") (pinfunction "CP_2") (pintype "passive"))
      (node (ref "U13") (pin "2") (pinfunction "CP_2") (pintype "passive"))
      (node (ref "U14") (pin "2") (pinfunction "CP_2") (pintype "passive"))
      (node (ref "U15") (pin "2") (pinfunction "CP_2") (pintype "passive"))
      (node (ref "U5") (pin "2") (pinfunction "CP_2") (pintype "passive"))
      (node (ref "U6") (pin "2") (pinfunction "CP_2") (pintype "passive"))
      (node (ref "U7") (pin "2") (pinfunction "CP_2") (pintype "passive"))
      (node (ref "U8") (pin "2") (pinfunction "CP_2") (pintype "passive"))
      (node (ref "U9") (pin "2") (pinfunction "CP_2") (pintype "passive"))
    )
    (net (code "8") (name "/SPI1_MISO") (class "Default")
      (node (ref "U1") (pin "16") (pinfunction "PA6_16") (pintype "bidirectional"))
      (node (ref "U5") (pin "9") (pinfunction "Q7_9") (pintype "passive"))
    )
    (net (code "9") (name "/SWCLK") (class "Default")
      (node (ref "U1") (pin "37") (pinfunction "PA14_37") (pintype "bidirectional"))
      (node (ref "U2") (pin "1") (pinfunction "1_1") (pintype "passive"))
    )
    (net (code "10") (name "/SWDIO") (class "Default")
      (node (ref "U1") (pin "34") (pinfunction "PA13_34") (pintype "bidirectional"))
      (node (ref "U2") (pin "2") (pinfunction "2_2") (pintype "passive"))
    )
    (net (code "11") (name "/UART_RX") (class "Default")
      (node (ref "U1") (pin "31") (pinfunction "PA10_31") (pintype "bidirectional"))
      (node (ref "U3") (pin "2") (pinfunction "2_2") (pintype "passive"))
    )
    (net (code "12") (name "/UART_TX") (class "Default")
      (node (ref "U1") (pin "30") (pinfunction "PA9_30") (pintype "bidirectional"))
      (node (ref "U3") (pin "1") (pinfunction "1_1") (pintype "passive"))
    )
    (net (code "13") (name "/USB_D+") (class "Default")
      (node (ref "R7") (pin "1") (pinfunction "1_1") (pintype "passive"))
      (node (ref "U1") (pin "33") (pinfunction "PA12_33") (pintype "bidirectional"))
    )
    (net (code "14") (name "/USB_D-") (class "Default")
      (node (ref "R2") (pin "1") (pinfunction "1_1") (pintype "passive"))
      (node (ref "U1") (pin "32") (pinfunction "PA11_32") (pintype "bidirectional"))
    )
    (net (code "15") (name "/USB_PORT_D+") (class "Default")
      (node (ref "R4") (pin "1") (pinfunction "1_1") (pintype "passive"))
      (node (ref "R7") (pin "2") (pinfunction "2_2") (pintype "passive"))
      (node (ref "USB1") (pin "A6") (pinfunction "D+_A6") (pintype "passive"))
      (node (ref "USB1") (pin "B6") (pinfunction "D+_B6") (pintype "passive"))
    )
    (net (code "16") (name "/USB_PORT_D-") (class "Default")
      (node (ref "R2") (pin "2") (pinfunction "2_2") (pintype "passive"))
      (node (ref "USB1") (pin "A7") (pinfunction "D-_A7") (pintype "passive"))
      (node (ref "USB1") (pin "B7") (pinfunction "D-_B7") (pintype "passive"))
    )
    (net (code "17") (name "GND") (class "Default")
      (node (ref "C1") (pin "1") (pinfunction "1_1") (pintype "passive"))
      (node (ref "C10") (pin "1") (pinfunction "1_1") (pintype "passive"))
      (node (ref "C11") (pin "2") (pinfunction "2_2") (pintype "passive"))
      (node (ref "C2") (pin "1") (pinfunction "1_1") (pintype "passive"))
      (node (ref "C3") (pin "1") (pinfunction "1_1") (pintype "passive"))
      (node (ref "C4") (pin "1") (pinfunction "1_1") (pintype "passive"))
      (node (ref "C5") (pin "1") (pinfunction "1_1") (pintype "passive"))
      (node (ref "C6") (pin "1") (pinfunction "1_1") (pintype "passive"))
      (node (ref "C7") (pin "1") (pinfunction "1_1") (pintype "passive"))
      (node (ref "C8") (pin "1") (pinfunction "1_1") (pintype "passive"))
      (node (ref "C9") (pin "1") (pinfunction "1_1") (pintype "passive"))
      (node (ref "R1") (pin "2") (pinfunction "2_2") (pintype "passive"))
      (node (ref "R3") (pin "1") (pinfunction "1_1") (pintype "passive"))
      (node (ref "SW1") (pin "1") (pinfunction "1_1") (pintype "passive"))
      (node (ref "SW10") (pin "1") (pinfunction "1_1") (pintype "passive"))
      (node (ref "SW11") (pin "1") (pinfunction "1_1") (pintype "passive"))
      (node (ref "SW12") (pin "1") (pinfunction "1_1") (pintype "passive"))
      (node (ref "SW13") (pin "1") (pinfunction "1_1") (pintype "passive"))
      (node (ref "SW14") (pin "1") (pinfunction "1_1") (pintype "passive"))
      (node (ref "SW15") (pin "1") (pinfunction "1_1") (pintype "passive"))
      (node (ref "SW16") (pin "1") (pinfunction "1_1") (pintype "passive"))
      (node (ref "SW17") (pin "1") (pinfunction "1_1") (pintype "passive"))
      (node (ref "SW18") (pin "1") (pinfunction "1_1") (pintype "passive"))
      (node (ref "SW19") (pin "1") (pinfunction "1_1") (pintype "passive"))
      (node (ref "SW2") (pin "1") (pinfunction "1_1") (pintype "passive"))
      (node (ref "SW20") (pin "1") (pinfunction "1_1") (pintype "passive"))
      (node (ref "SW21") (pin "1") (pinfunction "1_1") (pintype "passive"))
      (node (ref "SW22") (pin "1") (pinfunction "1_1") (pintype "passive"))
      (node (ref "SW23") (pin "1") (pinfunction "1_1") (pintype "passive"))
      (node (ref "SW24") (pin "1") (pinfunction "1_1") (pintype "passive"))
      (node (ref "SW25") (pin "1") (pinfunction "1_1") (pintype "passive"))
      (node (ref "SW26") (pin "1") (pinfunction "1_1") (pintype "passive"))
      (node (ref "SW27") (pin "1") (pinfunction "1_1") (pintype "passive"))
      (node (ref "SW28") (pin "1") (pinfunction "1_1") (pintype "passive"))
      (node (ref "SW29") (pin "1") (pinfunction "1_1") (pintype "passive"))
      (node (ref "SW3") (pin "1") (pinfunction "1_1") (pintype "passive"))
      (node (ref "SW30") (pin "1") (pinfunction "1_1") (pintype "passive"))
      (node (ref "SW31") (pin "1") (pinfunction "1_1") (pintype "passive"))
      (node (ref "SW32") (pin "1") (pinfunction "1_1") (pintype "passive"))
      (node (ref "SW33") (pin "1") (pinfunction "1_1") (pintype "passive"))
      (node (ref "SW34") (pin "1") (pinfunction "1_1") (pintype "passive"))
      (node (ref "SW35") (pin "1") (pinfunction "1_1") (pintype "passive"))
      (node (ref "SW36") (pin "1") (pinfunction "1_1") (pintype "passive"))
      (node (ref "SW37") (pin "1") (pinfunction "1_1") (pintype "passive"))
      (node (ref "SW38") (pin "1") (pinfunction "1_1") (pintype "passive"))
      (node (ref "SW39") (pin "1") (pinfunction "1_1") (pintype "passive"))
      (node (ref "SW4") (pin "1") (pinfunction "1_1") (pintype "passive"))
      (node (ref "SW40") (pin "1") (pinfunction "1_1") (pintype "passive"))
      (node (ref "SW41") (pin "1") (pinfunction "1_1") (pintype "passive"))
      (node (ref "SW42") (pin "1") (pinfunction "1_1") (pintype "passive"))
      (node (ref "SW43") (pin "1") (pinfunction "1_1") (pintype "passive"))
      (node (ref "SW44") (pin "1") (pinfunction "1_1") (pintype "passive"))
      (node (ref "SW45") (pin "1") (pinfunction "1_1") (pintype "passive"))
      (node (ref "SW46") (pin "1") (pinfunction "1_1") (pintype "passive"))
      (node (ref "SW47") (pin "1") (pinfunction "1_1") (pintype "passive"))
      (node (ref "SW48") (pin "1") (pinfunction "1_1") (pintype "passive"))
      (node (ref "SW49") (pin "1") (pinfunction "1_1") (pintype "passive"))
      (node (ref "SW5") (pin "1") (pinfunction "1_1") (pintype "passive"))
      (node (ref "SW50") (pin "1") (pinfunction "1_1") (pintype "passive"))
      (node (ref "SW51") (pin "1") (pinfunction "1_1") (pintype "passive"))
      (node (ref "SW52") (pin "1") (pinfunction "1_1") (pintype "passive"))
      (node (ref "SW53") (pin "1") (pinfunction "1_1") (pintype "passive"))
      (node (ref "SW54") (pin "1") (pinfunction "1_1") (pintype "passive"))
      (node (ref "SW55") (pin "1") (pinfunction "1_1") (pintype "passive"))
      (node (ref "SW56") (pin "1") (pinfunction "1_1") (pintype "passive"))
      (node (ref "SW57") (pin "1") (pinfunction "1_1") (pintype "passive"))
      (node (ref "SW58") (pin "1") (pinfunction "1_1") (pintype "passive"))
      (node (ref "SW59") (pin "1") (pinfunction "1_1") (pintype "passive"))
      (node (ref "SW6") (pin "1") (pinfunction "1_1") (pintype "passive"))
      (node (ref "SW60") (pin "1") (pinfunction "1_1") (pintype "passive"))
      (node (ref "SW61") (pin "1") (pinfunction "1_1") (pintype "passive"))
      (node (ref "SW62") (pin "1") (pinfunction "1_1") (pintype "passive"))
      (node (ref "SW63") (pin "1") (pinfunction "1_1") (pintype "passive"))
      (node (ref "SW64") (pin "1") (pinfunction "1_1") (pintype "passive"))
      (node (ref "SW65") (pin "1") (pinfunction "1_1") (pintype "passive"))
      (node (ref "SW66") (pin "1") (pinfunction "1_1") (pintype "passive"))
      (node (ref "SW67") (pin "1") (pinfunction "1_1") (pintype "passive"))
      (node (ref "SW68") (pin "1") (pinfunction "1_1") (pintype "passive"))
      (node (ref "SW69") (pin "1") (pinfunction "1_1") (pintype "passive"))
      (node (ref "SW7") (pin "1") (pinfunction "1_1") (pintype "passive"))
      (node (ref "SW70") (pin "1") (pinfunction "1_1") (pintype "passive"))
      (node (ref "SW71") (pin "1") (pinfunction "1_1") (pintype "passive"))
      (node (ref "SW72") (pin "1") (pinfunction "1_1") (pintype "passive"))
      (node (ref "SW73") (pin "1") (pinfunction "1_1") (pintype "passive"))
      (node (ref "SW74") (pin "1") (pinfunction "1_1") (pintype "passive"))
      (node (ref "SW75") (pin "1") (pinfunction "1_1") (pintype "passive"))
      (node (ref "SW76") (pin "1") (pinfunction "1_1") (pintype "passive"))
      (node (ref "SW77") (pin "1") (pinfunction "1_1") (pintype "passive"))
      (node (ref "SW78") (pin "1") (pinfunction "1_1") (pintype "passive"))
      (node (ref "SW79") (pin "1") (pinfunction "1_1") (pintype "passive"))
      (node (ref "SW8") (pin "1") (pinfunction "1_1") (pintype "passive"))
      (node (ref "SW80") (pin "1") (pinfunction "1_1") (pintype "passive"))
      (node (ref "SW81") (pin "1") (pinfunction "1_1") (pintype "passive"))
      (node (ref "SW82") (pin "1") (pinfunction "1_1") (pintype "passive"))
      (node (ref "SW83") (pin "1") (pinfunction "1_1") (pintype "passive"))
      (node (ref "SW84") (pin "1") (pinfunction "1_1") (pintype "passive"))
      (node (ref "SW85") (pin "1") (pinfunction "1_1") (pintype "passive"))
      (node (ref "SW86") (pin "1") (pinfunction "1_1") (pintype "passive"))
      (node (ref "SW87") (pin "1") (pinfunction "1_1") (pintype "passive"))
      (node (ref "SW9") (pin "1") (pinfunction "1_1") (pintype "passive"))
      (node (ref "U1") (pin "23") (pinfunction "VSS_1_23") (pintype "power_in"))
      (node (ref "U1") (pin "35") (pinfunction "VSS_2_35") (pintype "power_in"))
      (node (ref "U1") (pin "44") (pinfunction "BOOT0_44") (pintype "input"))
      (node (ref "U1") (pin "47") (pinfunction "VSS_3_47") (pintype "power_in"))
      (node (ref "U1") (pin "8") (pinfunction "VSSA_8") (pintype "power_in"))
      (node (ref "U10") (pin "8") (pinfunction "GND_8") (pintype "passive"))
      (node (ref "U11") (pin "8") (pinfunction "GND_8") (pintype "passive"))
      (node (ref "U12") (pin "8") (pinfunction "GND_8") (pintype "passive"))
      (node (ref "U13") (pin "8") (pinfunction "GND_8") (pintype "passive"))
      (node (ref "U14") (pin "8") (pinfunction "GND_8") (pintype "passive"))
      (node (ref "U15") (pin "8") (pinfunction "GND_8") (pintype "passive"))
      (node (ref "U2") (pin "3") (pinfunction "3_3") (pintype "passive"))
      (node (ref "U2") (pin "4") (pinfunction "4_4") (pintype "passive"))
      (node (ref "U2") (pin "5") (pinfunction "5_5") (pintype "passive"))
      (node (ref "U3") (pin "3") (pinfunction "3_3") (pintype "passive"))
      (node (ref "U3") (pin "4") (pinfunction "4_4") (pintype "passive"))
      (node (ref "U3") (pin "5") (pinfunction "5_5") (pintype "passive"))
      (node (ref "U4") (pin "2") (pinfunction "GND_2") (pintype "passive"))
      (node (ref "U5") (pin "8") (pinfunction "GND_8") (pintype "passive"))
      (node (ref "U6") (pin "8") (pinfunction "GND_8") (pintype "passive"))
      (node (ref "U7") (pin "8") (pinfunction "GND_8") (pintype "passive"))
      (node (ref "U8") (pin "8") (pinfunction "GND_8") (pintype "passive"))
      (node (ref "U9") (pin "8") (pinfunction "GND_8") (pintype "passive"))
      (node (ref "USB1") (pin "1") (pinfunction "SH1_1") (pintype "passive"))
      (node (ref "USB1") (pin "2") (pinfunction "SH2_2") (pintype "passive"))
      (node (ref "USB1") (pin "3") (pinfunction "SH3_3") (pintype "passive"))
      (node (ref "USB1") (pin "4") (pinfunction "SH4_4") (pintype "passive"))
      (node (ref "USB1") (pin "A1") (pinfunction "GND_A1") (pintype "passive"))
      (node (ref "USB1") (pin "A12") (pinfunction "GND_A12") (pintype "passive"))
      (node (ref "USB1") (pin "B1") (pinfunction "GND_B1") (pintype "passive"))
      (node (ref "USB1") (pin "B12") (pinfunction "GND_B12") (pintype "passive"))
      (node (ref "Y1") (pin "2") (pinfunction "2_2") (pintype "passive"))
    )
    (net (code "18") (name "Net-(D1-1)") (class "Default")
      (node (ref "D1") (pin "A") (pinfunction "1_A") (pintype "passive"))
      (node (ref "R5") (pin "2") (pinfunction "2_2") (pintype "passive"))
    )
    (net (code "19") (name "Net-(U1A-NRST)") (class "Default")
      (node (ref "C11") (pin "1") (pinfunction "1_1") (pintype "passive"))
      (node (ref "R6") (pin "1") (pinfunction "1_1") (pintype "passive"))
      (node (ref "U1") (pin "7") (pinfunction "NRST_7") (pintype "bidirectional"))
    )
    (net (code "20") (name "Net-(U4-BYPASS)") (class "Default")
      (node (ref "C8") (pin "2") (pinfunction "2_2") (pintype "passive"))
      (node (ref "U4") (pin "4") (pinfunction "BYPASS_4") (pintype "passive"))
    )
    (net (code "21") (name "Net-(U5-D0)") (class "Default")
      (node (ref "REG1") (pin "8") (pinfunction "8_8") (pintype "passive"))
      (node (ref "SW43") (pin "2") (pinfunction "2_2") (pintype "passive"))
      (node (ref "U5") (pin "11") (pinfunction "D0_11") (pintype "passive"))
    )
    (net (code "22") (name "Net-(U5-D1)") (class "Default")
      (node (ref "REG1") (pin "7") (pinfunction "7_7") (pintype "passive"))
      (node (ref "SW42") (pin "2") (pinfunction "2_2") (pintype "passive"))
      (node (ref "U5") (pin "12") (pinfunction "D1_12") (pintype "passive"))
    )
    (net (code "23") (name "Net-(U5-D2)") (class "Default")
      (node (ref "REG1") (pin "6") (pinfunction "6_6") (pintype "passive"))
      (node (ref "SW41") (pin "2") (pinfunction "2_2") (pintype "passive"))
      (node (ref "U5") (pin "13") (pinfunction "D2_13") (pintype "passive"))
    )
    (net (code "24") (name "Net-(U5-D3)") (class "Default")
      (node (ref "REG1") (pin "5") (pinfunction "5_5") (pintype "passive"))
      (node (ref "SW40") (pin "2") (pinfunction "2_2") (pintype "passive"))
      (node (ref "U5") (pin "14") (pinfunction "D3_14") (pintype "passive"))
    )
    (net (code "25") (name "Net-(U5-D4)") (class "Default")
      (node (ref "REG7") (pin "8") (pinfunction "8_8") (pintype "passive"))
      (node (ref "SW39") (pin "2") (pinfunction "2_2") (pintype "passive"))
      (node (ref "U5") (pin "3") (pinfunction "D4_3") (pintype "passive"))
    )
    (net (code "26") (name "Net-(U5-D5)") (class "Default")
      (node (ref "REG7") (pin "7") (pinfunction "7_7") (pintype "passive"))
      (node (ref "SW38") (pin "2") (pinfunction "2_2") (pintype "passive"))
      (node (ref "U5") (pin "4") (pinfunction "D5_4") (pintype "passive"))
    )
    (net (code "27") (name "Net-(U5-D6)") (class "Default")
      (node (ref "REG7") (pin "6") (pinfunction "6_6") (pintype "passive"))
      (node (ref "SW37") (pin "2") (pinfunction "2_2") (pintype "passive"))
      (node (ref "U5") (pin "5") (pinfunction "D6_5") (pintype "passive"))
    )
    (net (code "28") (name "Net-(U5-D7)") (class "Default")
      (node (ref "REG7") (pin "5") (pinfunction "5_5") (pintype "passive"))
      (node (ref "SW36") (pin "2") (pinfunction "2_2") (pintype "passive"))
      (node (ref "U5") (pin "6") (pinfunction "D7_6") (pintype "passive"))
    )
    (net (code "29") (name "Net-(U5-DS)") (class "Default")
      (node (ref "U5") (pin "10") (pinfunction "DS_10") (pintype "passive"))
      (node (ref "U6") (pin "9") (pinfunction "Q7_9") (pintype "passive"))
    )
    (net (code "30") (name "Net-(U6-D0)") (class "Default")
      (node (ref "REG2") (pin "8") (pinfunction "8_8") (pintype "passive"))
      (node (ref "SW8") (pin "2") (pinfunction "2_2") (pintype "passive"))
      (node (ref "U6") (pin "11") (pinfunction "D0_11") (pintype "passive"))
    )
    (net (code "31") (name "Net-(U6-D1)") (class "Default")
      (node (ref "REG2") (pin "7") (pinfunction "7_7") (pintype "passive"))
      (node (ref "SW7") (pin "2") (pinfunction "2_2") (pintype "passive"))
      (node (ref "U6") (pin "12") (pinfunction "D1_12") (pintype "passive"))
    )
    (net (code "32") (name "Net-(U6-D2)") (class "Default")
      (node (ref "REG2") (pin "6") (pinfunction "6_6") (pintype "passive"))
      (node (ref "SW6") (pin "2") (pinfunction "2_2") (pintype "passive"))
      (node (ref "U6") (pin "13") (pinfunction "D2_13") (pintype "passive"))
    )
    (net (code "33") (name "Net-(U6-D3)") (class "Default")
      (node (ref "REG2") (pin "5") (pinfunction "5_5") (pintype "passive"))
      (node (ref "SW5") (pin "2") (pinfunction "2_2") (pintype "passive"))
      (node (ref "U6") (pin "14") (pinfunction "D3_14") (pintype "passive"))
    )
    (net (code "34") (name "Net-(U6-D4)") (class "Default")
      (node (ref "REG8") (pin "8") (pinfunction "8_8") (pintype "passive"))
      (node (ref "SW4") (pin "2") (pinfunction "2_2") (pintype "passive"))
      (node (ref "U6") (pin "3") (pinfunction "D4_3") (pintype "passive"))
    )
    (net (code "35") (name "Net-(U6-D5)") (class "Default")
      (node (ref "REG8") (pin "7") (pinfunction "7_7") (pintype "passive"))
      (node (ref "SW3") (pin "2") (pinfunction "2_2") (pintype "passive"))
      (node (ref "U6") (pin "4") (pinfunction "D5_4") (pintype "passive"))
    )
    (net (code "36") (name "Net-(U6-D6)") (class "Default")
      (node (ref "REG8") (pin "6") (pinfunction "6_6") (pintype "passive"))
      (node (ref "SW2") (pin "2") (pinfunction "2_2") (pintype "passive"))
      (node (ref "U6") (pin "5") (pinfunction "D6_5") (pintype "passive"))
    )
    (net (code "37") (name "Net-(U6-D7)") (class "Default")
      (node (ref "REG8") (pin "5") (pinfunction "5_5") (pintype "passive"))
      (node (ref "SW1") (pin "2") (pinfunction "2_2") (pintype "passive"))
      (node (ref "U6") (pin "6") (pinfunction "D7_6") (pintype "passive"))
    )
    (net (code "38") (name "Net-(U6-DS)") (class "Default")
      (node (ref "U6") (pin "10") (pinfunction "DS_10") (pintype "passive"))
      (node (ref "U7") (pin "9") (pinfunction "Q7_9") (pintype "passive"))
    )
    (net (code "39") (name "Net-(U7-D0)") (class "Default")
      (node (ref "REG3") (pin "8") (pinfunction "8_8") (pintype "passive"))
      (node (ref "SW16") (pin "2") (pinfunction "2_2") (pintype "passive"))
      (node (ref "U7") (pin "11") (pinfunction "D0_11") (pintype "passive"))
    )
    (net (code "40") (name "Net-(U7-D1)") (class "Default")
      (node (ref "REG3") (pin "7") (pinfunction "7_7") (pintype "passive"))
      (node (ref "SW15") (pin "2") (pinfunction "2_2") (pintype "passive"))
      (node (ref "U7") (pin "12") (pinfunction "D1_12") (pintype "passive"))
    )
    (net (code "41") (name "Net-(U7-D2)") (class "Default")
      (node (ref "REG3") (pin "6") (pinfunction "6_6") (pintype "passive"))
      (node (ref "SW14") (pin "2") (pinfunction "2_2") (pintype "passive"))
      (node (ref "U7") (pin "13") (pinfunction "D2_13") (pintype "passive"))
    )
    (net (code "42") (name "Net-(U7-D3)") (class "Default")
      (node (ref "REG3") (pin "5") (pinfunction "5_5") (pintype "passive"))
      (node (ref "SW13") (pin "2") (pinfunction "2_2") (pintype "passive"))
      (node (ref "U7") (pin "14") (pinfunction "D3_14") (pintype "passive"))
    )
    (net (code "43") (name "Net-(U7-D4)") (class "Default")
      (node (ref "REG9") (pin "8") (pinfunction "8_8") (pintype "passive"))
      (node (ref "SW12") (pin "2") (pinfunction "2_2") (pintype "passive"))
      (node (ref "U7") (pin "3") (pinfunction "D4_3") (pintype "passive"))
    )
    (net (code "44") (name "Net-(U7-D5)") (class "Default")
      (node (ref "REG9") (pin "7") (pinfunction "7_7") (pintype "passive"))
      (node (ref "SW11") (pin "2") (pinfunction "2_2") (pintype "passive"))
      (node (ref "U7") (pin "4") (pinfunction "D5_4") (pintype "passive"))
    )
    (net (code "45") (name "Net-(U7-D6)") (class "Default")
      (node (ref "REG9") (pin "6") (pinfunction "6_6") (pintype "passive"))
      (node (ref "SW10") (pin "2") (pinfunction "2_2") (pintype "passive"))
      (node (ref "U7") (pin "5") (pinfunction "D6_5") (pintype "passive"))
    )
    (net (code "46") (name "Net-(U7-D7)") (class "Default")
      (node (ref "REG9") (pin "5") (pinfunction "5_5") (pintype "passive"))
      (node (ref "SW9") (pin "2") (pinfunction "2_2") (pintype "passive"))
      (node (ref "U7") (pin "6") (pinfunction "D7_6") (pintype "passive"))
    )
    (net (code "47") (name "Net-(U7-DS)") (class "Default")
      (node (ref "U7") (pin "10") (pinfunction "DS_10") (pintype "passive"))
      (node (ref "U8") (pin "9") (pinfunction "Q7_9") (pintype "passive"))
    )
    (net (code "48") (name "Net-(U8-D0)") (class "Default")
      (node (ref "REG4") (pin "8") (pinfunction "8_8") (pintype "passive"))
      (node (ref "SW24") (pin "2") (pinfunction "2_2") (pintype "passive"))
      (node (ref "U8") (pin "11") (pinfunction "D0_11") (pintype "passive"))
    )
    (net (code "49") (name "Net-(U8-D1)") (class "Default")
      (node (ref "REG4") (pin "7") (pinfunction "7_7") (pintype "passive"))
      (node (ref "SW23") (pin "2") (pinfunction "2_2") (pintype "passive"))
      (node (ref "U8") (pin "12") (pinfunction "D1_12") (pintype "passive"))
    )
    (net (code "50") (name "Net-(U8-D2)") (class "Default")
      (node (ref "REG4") (pin "6") (pinfunction "6_6") (pintype "passive"))
      (node (ref "SW22") (pin "2") (pinfunction "2_2") (pintype "passive"))
      (node (ref "U8") (pin "13") (pinfunction "D2_13") (pintype "passive"))
    )
    (net (code "51") (name "Net-(U8-D3)") (class "Default")
      (node (ref "REG4") (pin "5") (pinfunction "5_5") (pintype "passive"))
      (node (ref "SW21") (pin "2") (pinfunction "2_2") (pintype "passive"))
      (node (ref "U8") (pin "14") (pinfunction "D3_14") (pintype "passive"))
    )
    (net (code "52") (name "Net-(U8-D4)") (class "Default")
      (node (ref "REG10") (pin "8") (pinfunction "8_8") (pintype "passive"))
      (node (ref "SW20") (pin "2") (pinfunction "2_2") (pintype "passive"))
      (node (ref "U8") (pin "3") (pinfunction "D4_3") (pintype "passive"))
    )
    (net (code "53") (name "Net-(U8-D5)") (class "Default")
      (node (ref "REG10") (pin "7") (pinfunction "7_7") (pintype "passive"))
      (node (ref "SW19") (pin "2") (pinfunction "2_2") (pintype "passive"))
      (node (ref "U8") (pin "4") (pinfunction "D5_4") (pintype "passive"))
    )
    (net (code "54") (name "Net-(U8-D6)") (class "Default")
      (node (ref "REG10") (pin "6") (pinfunction "6_6") (pintype "passive"))
      (node (ref "SW18") (pin "2") (pinfunction "2_2") (pintype "passive"))
      (node (ref "U8") (pin "5") (pinfunction "D6_5") (pintype "passive"))
    )
    (net (code "55") (name "Net-(U8-D7)") (class "Default")
      (node (ref "REG10") (pin "5") (pinfunction "5_5") (pintype "passive"))
      (node (ref "SW17") (pin "2") (pinfunction "2_2") (pintype "passive"))
      (node (ref "U8") (pin "6") (pinfunction "D7_6") (pintype "passive"))
    )
    (net (code "56") (name "Net-(U8-DS)") (class "Default")
      (node (ref "U8") (pin "10") (pinfunction "DS_10") (pintype "passive"))
      (node (ref "U9") (pin "9") (pinfunction "Q7_9") (pintype "passive"))
    )
    (net (code "57") (name "Net-(U9-D0)") (class "Default")
      (node (ref "REG5") (pin "8") (pinfunction "8_8") (pintype "passive"))
      (node (ref "SW32") (pin "2") (pinfunction "2_2") (pintype "passive"))
      (node (ref "U9") (pin "11") (pinfunction "D0_11") (pintype "passive"))
    )
    (net (code "58") (name "Net-(U9-D1)") (class "Default")
      (node (ref "REG5") (pin "7") (pinfunction "7_7") (pintype "passive"))
      (node (ref "SW31") (pin "2") (pinfunction "2_2") (pintype "passive"))
      (node (ref "U9") (pin "12") (pinfunction "D1_12") (pintype "passive"))
    )
    (net (code "59") (name "Net-(U9-D2)") (class "Default")
      (node (ref "REG5") (pin "6") (pinfunction "6_6") (pintype "passive"))
      (node (ref "SW30") (pin "2") (pinfunction "2_2") (pintype "passive"))
      (node (ref "U9") (pin "13") (pinfunction "D2_13") (pintype "passive"))
    )
    (net (code "60") (name "Net-(U9-D3)") (class "Default")
      (node (ref "REG5") (pin "5") (pinfunction "5_5") (pintype "passive"))
      (node (ref "SW29") (pin "2") (pinfunction "2_2") (pintype "passive"))
      (node (ref "U9") (pin "14") (pinfunction "D3_14") (pintype "passive"))
    )
    (net (code "61") (name "Net-(U9-D4)") (class "Default")
      (node (ref "REG11") (pin "8") (pinfunction "8_8") (pintype "passive"))
      (node (ref "SW28") (pin "2") (pinfunction "2_2") (pintype "passive"))
      (node (ref "U9") (pin "3") (pinfunction "D4_3") (pintype "passive"))
    )
    (net (code "62") (name "Net-(U9-D5)") (class "Default")
      (node (ref "REG11") (pin "7") (pinfunction "7_7") (pintype "passive"))
      (node (ref "SW27") (pin "2") (pinfunction "2_2") (pintype "passive"))
      (node (ref "U9") (pin "4") (pinfunction "D5_4") (pintype "passive"))
    )
    (net (code "63") (name "Net-(U9-D6)") (class "Default")
      (node (ref "REG11") (pin "6") (pinfunction "6_6") (pintype "passive"))
      (node (ref "SW26") (pin "2") (pinfunction "2_2") (pintype "passive"))
      (node (ref "U9") (pin "5") (pinfunction "D6_5") (pintype "passive"))
    )
    (net (code "64") (name "Net-(U9-D7)") (class "Default")
      (node (ref "REG11") (pin "5") (pinfunction "5_5") (pintype "passive"))
      (node (ref "SW25") (pin "2") (pinfunction "2_2") (pintype "passive"))
      (node (ref "U9") (pin "6") (pinfunction "D7_6") (pintype "passive"))
    )
    (net (code "65") (name "Net-(U10-D0)") (class "Default")
      (node (ref "REG6") (pin "8") (pinfunction "8_8") (pintype "passive"))
      (node (ref "SW48") (pin "2") (pinfunction "2_2") (pintype "passive"))
      (node (ref "U10") (pin "11") (pinfunction "D0_11") (pintype "passive"))
    )
    (net (code "66") (name "Net-(U10-D1)") (class "Default")
      (node (ref "REG6") (pin "7") (pinfunction "7_7") (pintype "passive"))
      (node (ref "SW47") (pin "2") (pinfunction "2_2") (pintype "passive"))
      (node (ref "U10") (pin "12") (pinfunction "D1_12") (pintype "passive"))
    )
    (net (code "67") (name "Net-(U10-D2)") (class "Default")
      (node (ref "REG6") (pin "6") (pinfunction "6_6") (pintype "passive"))
      (node (ref "SW46") (pin "2") (pinfunction "2_2") (pintype "passive"))
      (node (ref "U10") (pin "13") (pinfunction "D2_13") (pintype "passive"))
    )
    (net (code "68") (name "Net-(U10-D3)") (class "Default")
      (node (ref "REG6") (pin "5") (pinfunction "5_5") (pintype "passive"))
      (node (ref "SW45") (pin "2") (pinfunction "2_2") (pintype "passive"))
      (node (ref "U10") (pin "14") (pinfunction "D3_14") (pintype "passive"))
    )
    (net (code "69") (name "Net-(U10-D4)") (class "Default")
      (node (ref "REG12") (pin "8") (pinfunction "8_8") (pintype "passive"))
      (node (ref "SW44") (pin "2") (pinfunction "2_2") (pintype "passive"))
      (node (ref "U10") (pin "3") (pinfunction "D4_3") (pintype "passive"))
    )
    (net (code "70") (name "Net-(U10-D5)") (class "Default")
      (node (ref "REG12") (pin "7") (pinfunction "7_7") (pintype "passive"))
      (node (ref "SW35") (pin "2") (pinfunction "2_2") (pintype "passive"))
      (node (ref "U10") (pin "4") (pinfunction "D5_4") (pintype "passive"))
    )
    (net (code "71") (name "Net-(U10-D6)") (class "Default")
      (node (ref "REG12") (pin "6") (pinfunction "6_6") (pintype "passive"))
      (node (ref "SW34") (pin "2") (pinfunction "2_2") (pintype "passive"))
      (node (ref "U10") (pin "5") (pinfunction "D6_5") (pintype "passive"))
    )
    (net (code "72") (name "Net-(U10-D7)") (class "Default")
      (node (ref "REG12") (pin "5") (pinfunction "5_5") (pintype "passive"))
      (node (ref "SW33") (pin "2") (pinfunction "2_2") (pintype "passive"))
      (node (ref "U10") (pin "6") (pinfunction "D7_6") (pintype "passive"))
    )
    (net (code "73") (name "Net-(U10-Q7)") (class "Default")
      (node (ref "U10") (pin "9") (pinfunction "Q7_9") (pintype "passive"))
      (node (ref "U9") (pin "10") (pinfunction "DS_10") (pintype "passive"))
    )
    (net (code "74") (name "Net-(U11-D0)") (class "Default")
      (node (ref "REG13") (pin "8") (pinfunction "8_8") (pintype "passive"))
      (node (ref "SW62") (pin "2") (pinfunction "2_2") (pintype "passive"))
      (node (ref "U11") (pin "11") (pinfunction "D0_11") (pintype "passive"))
    )
    (net (code "75") (name "Net-(U11-D1)") (class "Default")
      (node (ref "REG13") (pin "7") (pinfunction "7_7") (pintype "passive"))
      (node (ref "SW61") (pin "2") (pinfunction "2_2") (pintype "passive"))
      (node (ref "U11") (pin "12") (pinfunction "D1_12") (pintype "passive"))
    )
    (net (code "76") (name "Net-(U11-D2)") (class "Default")
      (node (ref "REG13") (pin "6") (pinfunction "6_6") (pintype "passive"))
      (node (ref "SW60") (pin "2") (pinfunction "2_2") (pintype "passive"))
      (node (ref "U11") (pin "13") (pinfunction "D2_13") (pintype "passive"))
    )
    (net (code "77") (name "Net-(U11-D3)") (class "Default")
      (node (ref "REG13") (pin "5") (pinfunction "5_5") (pintype "passive"))
      (node (ref "SW59") (pin "2") (pinfunction "2_2") (pintype "passive"))
      (node (ref "U11") (pin "14") (pinfunction "D3_14") (pintype "passive"))
    )
    (net (code "78") (name "Net-(U11-D4)") (class "Default")
      (node (ref "REG18") (pin "8") (pinfunction "8_8") (pintype "passive"))
      (node (ref "SW58") (pin "2") (pinfunction "2_2") (pintype "passive"))
      (node (ref "U11") (pin "3") (pinfunction "D4_3") (pintype "passive"))
    )
    (net (code "79") (name "Net-(U11-D5)") (class "Default")
      (node (ref "REG18") (pin "7") (pinfunction "7_7") (pintype "passive"))
      (node (ref "SW51") (pin "2") (pinfunction "2_2") (pintype "passive"))
      (node (ref "U11") (pin "4") (pinfunction "D5_4") (pintype "passive"))
    )
    (net (code "80") (name "Net-(U11-D6)") (class "Default")
      (node (ref "REG18") (pin "6") (pinfunction "6_6") (pintype "passive"))
      (node (ref "SW50") (pin "2") (pinfunction "2_2") (pintype "passive"))
      (node (ref "U11") (pin "5") (pinfunction "D6_5") (pintype "passive"))
    )
    (net (code "81") (name "Net-(U11-D7)") (class "Default")
      (node (ref "REG18") (pin "5") (pinfunction "5_5") (pintype "passive"))
      (node (ref "SW49") (pin "2") (pinfunction "2_2") (pintype "passive"))
      (node (ref "U11") (pin "6") (pinfunction "D7_6") (pintype "passive"))
    )
    (net (code "82") (name "Net-(U11-DS)") (class "Default")
      (node (ref "U11") (pin "10") (pinfunction "DS_10") (pintype "passive"))
      (node (ref "U12") (pin "9") (pinfunction "Q7_9") (pintype "passive"))
    )
    (net (code "83") (name "Net-(U12-D0)") (class "Default")
      (node (ref "REG14") (pin "8") (pinfunction "8_8") (pintype "passive"))
      (node (ref "SW56") (pin "2") (pinfunction "2_2") (pintype "passive"))
      (node (ref "U12") (pin "11") (pinfunction "D0_11") (pintype "passive"))
    )
    (net (code "84") (name "Net-(U12-D1)") (class "Default")
      (node (ref "REG14") (pin "7") (pinfunction "7_7") (pintype "passive"))
      (node (ref "SW55") (pin "2") (pinfunction "2_2") (pintype "passive"))
      (node (ref "U12") (pin "12") (pinfunction "D1_12") (pintype "passive"))
    )
    (net (code "85") (name "Net-(U12-D2)") (class "Default")
      (node (ref "REG14") (pin "6") (pinfunction "6_6") (pintype "passive"))
      (node (ref "SW65") (pin "2") (pinfunction "2_2") (pintype "passive"))
      (node (ref "U12") (pin "13") (pinfunction "D2_13") (pintype "passive"))
    )
    (net (code "86") (name "Net-(U12-D3)") (class "Default")
      (node (ref "REG14") (pin "5") (pinfunction "5_5") (pintype "passive"))
      (node (ref "SW54") (pin "2") (pinfunction "2_2") (pintype "passive"))
      (node (ref "U12") (pin "14") (pinfunction "D3_14") (pintype "passive"))
    )
    (net (code "87") (name "Net-(U12-D4)") (class "Default")
      (node (ref "REG19") (pin "8") (pinfunction "8_8") (pintype "passive"))
      (node (ref "SW64") (pin "2") (pinfunction "2_2") (pintype "passive"))
      (node (ref "U12") (pin "3") (pinfunction "D4_3") (pintype "passive"))
    )
    (net (code "88") (name "Net-(U12-D5)") (class "Default")
      (node (ref "REG19") (pin "7") (pinfunction "7_7") (pintype "passive"))
      (node (ref "SW63") (pin "2") (pinfunction "2_2") (pintype "passive"))
      (node (ref "U12") (pin "4") (pinfunction "D5_4") (pintype "passive"))
    )
    (net (code "89") (name "Net-(U12-D6)") (class "Default")
      (node (ref "REG19") (pin "6") (pinfunction "6_6") (pintype "passive"))
      (node (ref "SW53") (pin "2") (pinfunction "2_2") (pintype "passive"))
      (node (ref "U12") (pin "5") (pinfunction "D6_5") (pintype "passive"))
    )
    (net (code "90") (name "Net-(U12-D7)") (class "Default")
      (node (ref "REG19") (pin "5") (pinfunction "5_5") (pintype "passive"))
      (node (ref "SW52") (pin "2") (pinfunction "2_2") (pintype "passive"))
      (node (ref "U12") (pin "6") (pinfunction "D7_6") (pintype "passive"))
    )
    (net (code "91") (name "Net-(U12-DS)") (class "Default")
      (node (ref "U12") (pin "10") (pinfunction "DS_10") (pintype "passive"))
      (node (ref "U13") (pin "9") (pinfunction "Q7_9") (pintype "passive"))
    )
    (net (code "92") (name "Net-(U13-D0)") (class "Default")
      (node (ref "REG15") (pin "8") (pinfunction "8_8") (pintype "passive"))
      (node (ref "SW72") (pin "2") (pinfunction "2_2") (pintype "passive"))
      (node (ref "U13") (pin "11") (pinfunction "D0_11") (pintype "passive"))
    )
    (net (code "93") (name "Net-(U13-D1)") (class "Default")
      (node (ref "REG15") (pin "7") (pinfunction "7_7") (pintype "passive"))
      (node (ref "SW71") (pin "2") (pinfunction "2_2") (pintype "passive"))
      (node (ref "U13") (pin "12") (pinfunction "D1_12") (pintype "passive"))
    )
    (net (code "94") (name "Net-(U13-D2)") (class "Default")
      (node (ref "REG15") (pin "6") (pinfunction "6_6") (pintype "passive"))
      (node (ref "SW70") (pin "2") (pinfunction "2_2") (pintype "passive"))
      (node (ref "U13") (pin "13") (pinfunction "D2_13") (pintype "passive"))
    )
    (net (code "95") (name "Net-(U13-D3)") (class "Default")
      (node (ref "REG15") (pin "5") (pinfunction "5_5") (pintype "passive"))
      (node (ref "SW69") (pin "2") (pinfunction "2_2") (pintype "passive"))
      (node (ref "U13") (pin "14") (pinfunction "D3_14") (pintype "passive"))
    )
    (net (code "96") (name "Net-(U13-D4)") (class "Default")
      (node (ref "REG20") (pin "8") (pinfunction "8_8") (pintype "passive"))
      (node (ref "SW68") (pin "2") (pinfunction "2_2") (pintype "passive"))
      (node (ref "U13") (pin "3") (pinfunction "D4_3") (pintype "passive"))
    )
    (net (code "97") (name "Net-(U13-D5)") (class "Default")
      (node (ref "REG20") (pin "7") (pinfunction "7_7") (pintype "passive"))
      (node (ref "SW67") (pin "2") (pinfunction "2_2") (pintype "passive"))
      (node (ref "U13") (pin "4") (pinfunction "D5_4") (pintype "passive"))
    )
    (net (code "98") (name "Net-(U13-D6)") (class "Default")
      (node (ref "REG20") (pin "6") (pinfunction "6_6") (pintype "passive"))
      (node (ref "SW66") (pin "2") (pinfunction "2_2") (pintype "passive"))
      (node (ref "U13") (pin "5") (pinfunction "D6_5") (pintype "passive"))
    )
    (net (code "99") (name "Net-(U13-D7)") (class "Default")
      (node (ref "REG20") (pin "5") (pinfunction "5_5") (pintype "passive"))
      (node (ref "SW57") (pin "2") (pinfunction "2_2") (pintype "passive"))
      (node (ref "U13") (pin "6") (pinfunction "D7_6") (pintype "passive"))
    )
    (net (code "100") (name "Net-(U13-DS)") (class "Default")
      (node (ref "U13") (pin "10") (pinfunction "DS_10") (pintype "passive"))
      (node (ref "U14") (pin "9") (pinfunction "Q7_9") (pintype "passive"))
    )
    (net (code "101") (name "Net-(U14-D0)") (class "Default")
      (node (ref "REG17") (pin "8") (pinfunction "8_8") (pintype "passive"))
      (node (ref "SW84") (pin "2") (pinfunction "2_2") (pintype "passive"))
      (node (ref "U14") (pin "11") (pinfunction "D0_11") (pintype "passive"))
    )
    (net (code "102") (name "Net-(U14-D1)") (class "Default")
      (node (ref "REG17") (pin "7") (pinfunction "7_7") (pintype "passive"))
      (node (ref "SW83") (pin "2") (pinfunction "2_2") (pintype "passive"))
      (node (ref "U14") (pin "12") (pinfunction "D1_12") (pintype "passive"))
    )
    (net (code "103") (name "Net-(U14-D2)") (class "Default")
      (node (ref "REG17") (pin "6") (pinfunction "6_6") (pintype "passive"))
      (node (ref "SW78") (pin "2") (pinfunction "2_2") (pintype "passive"))
      (node (ref "U14") (pin "13") (pinfunction "D2_13") (pintype "passive"))
    )
    (net (code "104") (name "Net-(U14-D3)") (class "Default")
      (node (ref "REG17") (pin "5") (pinfunction "5_5") (pintype "passive"))
      (node (ref "SW77") (pin "2") (pinfunction "2_2") (pintype "passive"))
      (node (ref "U14") (pin "14") (pinfunction "D3_14") (pintype "passive"))
    )
    (net (code "105") (name "Net-(U14-D4)") (class "Default")
      (node (ref "REG21") (pin "8") (pinfunction "8_8") (pintype "passive"))
      (node (ref "SW76") (pin "2") (pinfunction "2_2") (pintype "passive"))
      (node (ref "U14") (pin "3") (pinfunction "D4_3") (pintype "passive"))
    )
    (net (code "106") (name "Net-(U14-D5)") (class "Default")
      (node (ref "REG21") (pin "7") (pinfunction "7_7") (pintype "passive"))
      (node (ref "SW75") (pin "2") (pinfunction "2_2") (pintype "passive"))
      (node (ref "U14") (pin "4") (pinfunction "D5_4") (pintype "passive"))
    )
    (net (code "107") (name "Net-(U14-D6)") (class "Default")
      (node (ref "REG21") (pin "6") (pinfunction "6_6") (pintype "passive"))
      (node (ref "SW74") (pin "2") (pinfunction "2_2") (pintype "passive"))
      (node (ref "U14") (pin "5") (pinfunction "D6_5") (pintype "passive"))
    )
    (net (code "108") (name "Net-(U14-D7)") (class "Default")
      (node (ref "REG21") (pin "5") (pinfunction "5_5") (pintype "passive"))
      (node (ref "SW73") (pin "2") (pinfunction "2_2") (pintype "passive"))
      (node (ref "U14") (pin "6") (pinfunction "D7_6") (pintype "passive"))
    )
    (net (code "109") (name "Net-(U14-DS)") (class "Default")
      (node (ref "U14") (pin "10") (pinfunction "DS_10") (pintype "passive"))
      (node (ref "U15") (pin "9") (pinfunction "Q7_9") (pintype "passive"))
    )
    (net (code "110") (name "Net-(U15-D0)") (class "Default")
      (node (ref "REG16") (pin "8") (pinfunction "8_8") (pintype "passive"))
      (node (ref "SW82") (pin "2") (pinfunction "2_2") (pintype "passive"))
      (node (ref "U15") (pin "11") (pinfunction "D0_11") (pintype "passive"))
    )
    (net (code "111") (name "Net-(U15-D1)") (class "Default")
      (node (ref "REG16") (pin "7") (pinfunction "7_7") (pintype "passive"))
      (node (ref "SW81") (pin "2") (pinfunction "2_2") (pintype "passive"))
      (node (ref "U15") (pin "12") (pinfunction "D1_12") (pintype "passive"))
    )
    (net (code "112") (name "Net-(U15-D2)") (class "Default")
      (node (ref "REG16") (pin "6") (pinfunction "6_6") (pintype "passive"))
      (node (ref "SW80") (pin "2") (pinfunction "2_2") (pintype "passive"))
      (node (ref "U15") (pin "13") (pinfunction "D2_13") (pintype "passive"))
    )
    (net (code "113") (name "Net-(U15-D3)") (class "Default")
      (node (ref "REG16") (pin "5") (pinfunction "5_5") (pintype "passive"))
      (node (ref "SW87") (pin "2") (pinfunction "2_2") (pintype "passive"))
      (node (ref "U15") (pin "14") (pinfunction "D3_14") (pintype "passive"))
    )
    (net (code "114") (name "Net-(U15-D4)") (class "Default")
      (node (ref "REG22") (pin "8") (pinfunction "8_8") (pintype "passive"))
      (node (ref "SW86") (pin "2") (pinfunction "2_2") (pintype "passive"))
      (node (ref "U15") (pin "3") (pinfunction "D4_3") (pintype "passive"))
    )
    (net (code "115") (name "Net-(U15-D5)") (class "Default")
      (node (ref "REG22") (pin "7") (pinfunction "7_7") (pintype "passive"))
      (node (ref "SW85") (pin "2") (pinfunction "2_2") (pintype "passive"))
      (node (ref "U15") (pin "4") (pinfunction "D5_4") (pintype "passive"))
    )
    (net (code "116") (name "Net-(U15-D6)") (class "Default")
      (node (ref "REG22") (pin "6") (pinfunction "6_6") (pintype "passive"))
      (node (ref "SW79") (pin "2") (pinfunction "2_2") (pintype "passive"))
      (node (ref "U15") (pin "5") (pinfunction "D6_5") (pintype "passive"))
    )
    (net (code "117") (name "Net-(U15-D7)") (class "Default")
      (node (ref "REG22") (pin "5") (pinfunction "5_5") (pintype "passive"))
      (node (ref "U15") (pin "6") (pinfunction "D7_6") (pintype "passive"))
    )
    (net (code "118") (name "Net-(USB1-CC1)") (class "Default")
      (node (ref "R1") (pin "1") (pinfunction "1_1") (pintype "passive"))
      (node (ref "USB1") (pin "A5") (pinfunction "CC1_A5") (pintype "passive"))
    )
    (net (code "119") (name "Net-(USB1-CC2)") (class "Default")
      (node (ref "R3") (pin "2") (pinfunction "2_2") (pintype "passive"))
      (node (ref "USB1") (pin "B5") (pinfunction "CC2_B5") (pintype "passive"))
    )
    (net (code "120") (name "VBUS") (class "Default")
      (node (ref "C10") (pin "2") (pinfunction "2_2") (pintype "passive"))
      (node (ref "C9") (pin "2") (pinfunction "2_2") (pintype "passive"))
      (node (ref "U4") (pin "1") (pinfunction "VIN_1") (pintype "passive"))
      (node (ref "U4") (pin "3") (pinfunction "ON/OFF_3") (pintype "passive"))
      (node (ref "USB1") (pin "A4") (pinfunction "VBUS_A4") (pintype "passive"))
      (node (ref "USB1") (pin "A9") (pinfunction "VBUS_A9") (pintype "passive"))
      (node (ref "USB1") (pin "B4") (pinfunction "VBUS_B4") (pintype "passive"))
      (node (ref "USB1") (pin "B9") (pinfunction "VBUS_B9") (pintype "passive"))
    )
    (net (code "121") (name "VCC_3V3") (class "Default")
      (node (ref "C1") (pin "2") (pinfunction "2_2") (pintype "passive"))
      (node (ref "C2") (pin "2") (pinfunction "2_2") (pintype "passive"))
      (node (ref "C3") (pin "2") (pinfunction "2_2") (pintype "passive"))
      (node (ref "C4") (pin "2") (pinfunction "2_2") (pintype "passive"))
      (node (ref "C5") (pin "2") (pinfunction "2_2") (pintype "passive"))
      (node (ref "C6") (pin "2") (pinfunction "2_2") (pintype "passive"))
      (node (ref "C7") (pin "2") (pinfunction "2_2") (pintype "passive"))
      (node (ref "D1") (pin "K") (pinfunction "2_K") (pintype "passive"))
      (node (ref "R4") (pin "2") (pinfunction "2_2") (pintype "passive"))
      (node (ref "R6") (pin "2") (pinfunction "2_2") (pintype "passive"))
      (node (ref "REG1") (pin "1") (pinfunction "1_1") (pintype "passive"))
      (node (ref "REG1") (pin "2") (pinfunction "2_2") (pintype "passive"))
      (node (ref "REG1") (pin "3") (pinfunction "3_3") (pintype "passive"))
      (node (ref "REG1") (pin "4") (pinfunction "4_4") (pintype "passive"))
      (node (ref "REG10") (pin "1") (pinfunction "1_1") (pintype "passive"))
      (node (ref "REG10") (pin "2") (pinfunction "2_2") (pintype "passive"))
      (node (ref "REG10") (pin "3") (pinfunction "3_3") (pintype "passive"))
      (node (ref "REG10") (pin "4") (pinfunction "4_4") (pintype "passive"))
      (node (ref "REG11") (pin "1") (pinfunction "1_1") (pintype "passive"))
      (node (ref "REG11") (pin "2") (pinfunction "2_2") (pintype "passive"))
      (node (ref "REG11") (pin "3") (pinfunction "3_3") (pintype "passive"))
      (node (ref "REG11") (pin "4") (pinfunction "4_4") (pintype "passive"))
      (node (ref "REG12") (pin "1") (pinfunction "1_1") (pintype "passive"))
      (node (ref "REG12") (pin "2") (pinfunction "2_2") (pintype "passive"))
      (node (ref "REG12") (pin "3") (pinfunction "3_3") (pintype "passive"))
      (node (ref "REG12") (pin "4") (pinfunction "4_4") (pintype "passive"))
      (node (ref "REG13") (pin "1") (pinfunction "1_1") (pintype "passive"))
      (node (ref "REG13") (pin "2") (pinfunction "2_2") (pintype "passive"))
      (node (ref "REG13") (pin "3") (pinfunction "3_3") (pintype "passive"))
      (node (ref "REG13") (pin "4") (pinfunction "4_4") (pintype "passive"))
      (node (ref "REG14") (pin "1") (pinfunction "1_1") (pintype "passive"))
      (node (ref "REG14") (pin "2") (pinfunction "2_2") (pintype "passive"))
      (node (ref "REG14") (pin "3") (pinfunction "3_3") (pintype "passive"))
      (node (ref "REG14") (pin "4") (pinfunction "4_4") (pintype "passive"))
      (node (ref "REG15") (pin "1") (pinfunction "1_1") (pintype "passive"))
      (node (ref "REG15") (pin "2") (pinfunction "2_2") (pintype "passive"))
      (node (ref "REG15") (pin "3") (pinfunction "3_3") (pintype "passive"))
      (node (ref "REG15") (pin "4") (pinfunction "4_4") (pintype "passive"))
      (node (ref "REG16") (pin "1") (pinfunction "1_1") (pintype "passive"))
      (node (ref "REG16") (pin "2") (pinfunction "2_2") (pintype "passive"))
      (node (ref "REG16") (pin "3") (pinfunction "3_3") (pintype "passive"))
      (node (ref "REG16") (pin "4") (pinfunction "4_4") (pintype "passive"))
      (node (ref "REG17") (pin "1") (pinfunction "1_1") (pintype "passive"))
      (node (ref "REG17") (pin "2") (pinfunction "2_2") (pintype "passive"))
      (node (ref "REG17") (pin "3") (pinfunction "3_3") (pintype "passive"))
      (node (ref "REG17") (pin "4") (pinfunction "4_4") (pintype "passive"))
      (node (ref "REG18") (pin "1") (pinfunction "1_1") (pintype "passive"))
      (node (ref "REG18") (pin "2") (pinfunction "2_2") (pintype "passive"))
      (node (ref "REG18") (pin "3") (pinfunction "3_3") (pintype "passive"))
      (node (ref "REG18") (pin "4") (pinfunction "4_4") (pintype "passive"))
      (node (ref "REG19") (pin "1") (pinfunction "1_1") (pintype "passive"))
      (node (ref "REG19") (pin "2") (pinfunction "2_2") (pintype "passive"))
      (node (ref "REG19") (pin "3") (pinfunction "3_3") (pintype "passive"))
      (node (ref "REG19") (pin "4") (pinfunction "4_4") (pintype "passive"))
      (node (ref "REG2") (pin "1") (pinfunction "1_1") (pintype "passive"))
      (node (ref "REG2") (pin "2") (pinfunction "2_2") (pintype "passive"))
      (node (ref "REG2") (pin "3") (pinfunction "3_3") (pintype "passive"))
      (node (ref "REG2") (pin "4") (pinfunction "4_4") (pintype "passive"))
      (node (ref "REG20") (pin "1") (pinfunction "1_1") (pintype "passive"))
      (node (ref "REG20") (pin "2") (pinfunction "2_2") (pintype "passive"))
      (node (ref "REG20") (pin "3") (pinfunction "3_3") (pintype "passive"))
      (node (ref "REG20") (pin "4") (pinfunction "4_4") (pintype "passive"))
      (node (ref "REG21") (pin "1") (pinfunction "1_1") (pintype "passive"))
      (node (ref "REG21") (pin "2") (pinfunction "2_2") (pintype "passive"))
      (node (ref "REG21") (pin "3") (pinfunction "3_3") (pintype "passive"))
      (node (ref "REG21") (pin "4") (pinfunction "4_4") (pintype "passive"))
      (node (ref "REG22") (pin "1") (pinfunction "1_1") (pintype "passive"))
      (node (ref "REG22") (pin "2") (pinfunction "2_2") (pintype "passive"))
      (node (ref "REG22") (pin "3") (pinfunction "3_3") (pintype "passive"))
      (node (ref "REG22") (pin "4") (pinfunction "4_4") (pintype "passive"))
      (node (ref "REG3") (pin "1") (pinfunction "1_1") (pintype "passive"))
      (node (ref "REG3") (pin "2") (pinfunction "2_2") (pintype "passive"))
      (node (ref "REG3") (pin "3") (pinfunction "3_3") (pintype "passive"))
      (node (ref "REG3") (pin "4") (pinfunction "4_4") (pintype "passive"))
      (node (ref "REG4") (pin "1") (pinfunction "1_1") (pintype "passive"))
      (node (ref "REG4") (pin "2") (pinfunction "2_2") (pintype "passive"))
      (node (ref "REG4") (pin "3") (pinfunction "3_3") (pintype "passive"))
      (node (ref "REG4") (pin "4") (pinfunction "4_4") (pintype "passive"))
      (node (ref "REG5") (pin "1") (pinfunction "1_1") (pintype "passive"))
      (node (ref "REG5") (pin "2") (pinfunction "2_2") (pintype "passive"))
      (node (ref "REG5") (pin "3") (pinfunction "3_3") (pintype "passive"))
      (node (ref "REG5") (pin "4") (pinfunction "4_4") (pintype "passive"))
      (node (ref "REG6") (pin "1") (pinfunction "1_1") (pintype "passive"))
      (node (ref "REG6") (pin "2") (pinfunction "2_2") (pintype "passive"))
      (node (ref "REG6") (pin "3") (pinfunction "3_3") (pintype "passive"))
      (node (ref "REG6") (pin "4") (pinfunction "4_4") (pintype "passive"))
      (node (ref "REG7") (pin "1") (pinfunction "1_1") (pintype "passive"))
      (node (ref "REG7") (pin "2") (pinfunction "2_2") (pintype "passive"))
      (node (ref "REG7") (pin "3") (pinfunction "3_3") (pintype "passive"))
      (node (ref "REG7") (pin "4") (pinfunction "4_4") (pintype "passive"))
      (node (ref "REG8") (pin "1") (pinfunction "1_1") (pintype "passive"))
      (node (ref "REG8") (pin "2") (pinfunction "2_2") (pintype "passive"))
      (node (ref "REG8") (pin "3") (pinfunction "3_3") (pintype "passive"))
      (node (ref "REG8") (pin "4") (pinfunction "4_4") (pintype "passive"))
      (node (ref "REG9") (pin "1") (pinfunction "1_1") (pintype "passive"))
      (node (ref "REG9") (pin "2") (pinfunction "2_2") (pintype "passive"))
      (node (ref "REG9") (pin "3") (pinfunction "3_3") (pintype "passive"))
      (node (ref "REG9") (pin "4") (pinfunction "4_4") (pintype "passive"))
      (node (ref "U1") (pin "1") (pinfunction "VBAT_1") (pintype "power_in"))
      (node (ref "U1") (pin "24") (pinfunction "VDD_1_24") (pintype "power_in"))
      (node (ref "U1") (pin "36") (pinfunction "VDD_2_36") (pintype "power_in"))
      (node (ref "U1") (pin "48") (pinfunction "VDD_3_48") (pintype "power_in"))
      (node (ref "U1") (pin "9") (pinfunction "VDDA_9") (pintype "power_in"))
      (node (ref "U10") (pin "16") (pinfunction "VCC_16") (pintype "passive"))
      (node (ref "U11") (pin "16") (pinfunction "VCC_16") (pintype "passive"))
      (node (ref "U12") (pin "16") (pinfunction "VCC_16") (pintype "passive"))
      (node (ref "U13") (pin "16") (pinfunction "VCC_16") (pintype "passive"))
      (node (ref "U14") (pin "16") (pinfunction "VCC_16") (pintype "passive"))
      (node (ref "U15") (pin "16") (pinfunction "VCC_16") (pintype "passive"))
      (node (ref "U4") (pin "5") (pinfunction "VOUT_5") (pintype "passive"))
      (node (ref "U5") (pin "16") (pinfunction "VCC_16") (pintype "passive"))
      (node (ref "U6") (pin "16") (pinfunction "VCC_16") (pintype "passive"))
      (node (ref "U7") (pin "16") (pinfunction "VCC_16") (pintype "passive"))
      (node (ref "U8") (pin "16") (pinfunction "VCC_16") (pintype "passive"))
      (node (ref "U9") (pin "16") (pinfunction "VCC_16") (pintype "passive"))
    )
    (net (code "122") (name "unconnected-(U1A-PA0-WKUP-Pad10)") (class "Default")
      (node (ref "U1") (pin "10") (pinfunction "PA0-WKUP_10") (pintype "bidirectional"))
    )
    (net (code "123") (name "unconnected-(U1A-PA1-Pad11)") (class "Default")
      (node (ref "U1") (pin "11") (pinfunction "PA1_11") (pintype "bidirectional"))
    )
    (net (code "124") (name "unconnected-(U1A-PA2-Pad12)") (class "Default")
      (node (ref "U1") (pin "12") (pinfunction "PA2_12") (pintype "bidirectional"))
    )
    (net (code "125") (name "unconnected-(U1A-PA3-Pad13)") (class "Default")
      (node (ref "U1") (pin "13") (pinfunction "PA3_13") (pintype "bidirectional"))
    )
    (net (code "126") (name "unconnected-(U1A-PA4-Pad14)") (class "Default")
      (node (ref "U1") (pin "14") (pinfunction "PA4_14") (pintype "bidirectional"))
    )
    (net (code "127") (name "unconnected-(U1A-PA7-Pad17)") (class "Default")
      (node (ref "U1") (pin "17") (pinfunction "PA7_17") (pintype "bidirectional"))
    )
    (net (code "128") (name "unconnected-(U1A-PA8-Pad29)") (class "Default")
      (node (ref "U1") (pin "29") (pinfunction "PA8_29") (pintype "bidirectional"))
    )
    (net (code "129") (name "unconnected-(U1A-PA15-Pad38)") (class "Default")
      (node (ref "U1") (pin "38") (pinfunction "PA15_38") (pintype "bidirectional"))
    )
    (net (code "130") (name "unconnected-(U1A-PB0-Pad18)") (class "Default")
      (node (ref "U1") (pin "18") (pinfunction "PB0_18") (pintype "bidirectional"))
    )
    (net (code "131") (name "unconnected-(U1A-PB1-Pad19)") (class "Default")
      (node (ref "U1") (pin "19") (pinfunction "PB1_19") (pintype "bidirectional"))
    )
    (net (code "132") (name "unconnected-(U1A-PB2-Pad20)") (class "Default")
      (node (ref "U1") (pin "20") (pinfunction "PB2_20") (pintype "bidirectional"))
    )
    (net (code "133") (name "unconnected-(U1A-PB5-Pad41)") (class "Default")
      (node (ref "U1") (pin "41") (pinfunction "PB5_41") (pintype "bidirectional"))
    )
    (net (code "134") (name "unconnected-(U1A-PB6-Pad42)") (class "Default")
      (node (ref "U1") (pin "42") (pinfunction "PB6_42") (pintype "bidirectional"))
    )
    (net (code "135") (name "unconnected-(U1A-PB7-Pad43)") (class "Default")
      (node (ref "U1") (pin "43") (pinfunction "PB7_43") (pintype "bidirectional"))
    )
    (net (code "136") (name "unconnected-(U1A-PB9-Pad46)") (class "Default")
      (node (ref "U1") (pin "46") (pinfunction "PB9_46") (pintype "bidirectional"))
    )
    (net (code "137") (name "unconnected-(U1A-PB10-Pad21)") (class "Default")
      (node (ref "U1") (pin "21") (pinfunction "PB10_21") (pintype "bidirectional"))
    )
    (net (code "138") (name "unconnected-(U1A-PB11-Pad22)") (class "Default")
      (node (ref "U1") (pin "22") (pinfunction "PB11_22") (pintype "bidirectional"))
    )
    (net (code "139") (name "unconnected-(U1A-PB12-Pad25)") (class "Default")
      (node (ref "U1") (pin "25") (pinfunction "PB12_25") (pintype "bidirectional"))
    )
    (net (code "140") (name "unconnected-(U1A-PB13-Pad26)") (class "Default")
      (node (ref "U1") (pin "26") (pinfunction "PB13_26") (pintype "bidirectional"))
    )
    (net (code "141") (name "unconnected-(U1A-PB14-Pad27)") (class "Default")
      (node (ref "U1") (pin "27") (pinfunction "PB14_27") (pintype "bidirectional"))
    )
    (net (code "142") (name "unconnected-(U1A-PB15-Pad28)") (class "Default")
      (node (ref "U1") (pin "28") (pinfunction "PB15_28") (pintype "bidirectional"))
    )
    (net (code "143") (name "unconnected-(U1A-PC13-TAMPER-RTC-Pad2)") (class "Default")
      (node (ref "U1") (pin "2") (pinfunction "PC13-TAMPER-RTC_2") (pintype "bidirectional"))
    )
    (net (code "144") (name "unconnected-(U1A-PC14-OSC32_IN-Pad3)") (class "Default")
      (node (ref "U1") (pin "3") (pinfunction "PC14-OSC32_IN_3") (pintype "bidirectional"))
    )
    (net (code "145") (name "unconnected-(U1A-PC15-OSC32_OUT-Pad4)") (class "Default")
      (node (ref "U1") (pin "4") (pinfunction "PC15-OSC32_OUT_4") (pintype "bidirectional"))
    )
    (net (code "146") (name "unconnected-(U5-Q7#-Pad7)") (class "Default")
      (node (ref "U5") (pin "7") (pinfunction "Q7#_7") (pintype "passive"))
    )
    (net (code "147") (name "unconnected-(U6-Q7#-Pad7)") (class "Default")
      (node (ref "U6") (pin "7") (pinfunction "Q7#_7") (pintype "passive"))
    )
    (net (code "148") (name "unconnected-(U7-Q7#-Pad7)") (class "Default")
      (node (ref "U7") (pin "7") (pinfunction "Q7#_7") (pintype "passive"))
    )
    (net (code "149") (name "unconnected-(U8-Q7#-Pad7)") (class "Default")
      (node (ref "U8") (pin "7") (pinfunction "Q7#_7") (pintype "passive"))
    )
    (net (code "150") (name "unconnected-(U9-Q7#-Pad7)") (class "Default")
      (node (ref "U9") (pin "7") (pinfunction "Q7#_7") (pintype "passive"))
    )
    (net (code "151") (name "unconnected-(U10-Q7#-Pad7)") (class "Default")
      (node (ref "U10") (pin "7") (pinfunction "Q7#_7") (pintype "passive"))
    )
    (net (code "152") (name "unconnected-(U11-Q7#-Pad7)") (class "Default")
      (node (ref "U11") (pin "7") (pinfunction "Q7#_7") (pintype "passive"))
    )
    (net (code "153") (name "unconnected-(U12-Q7#-Pad7)") (class "Default")
      (node (ref "U12") (pin "7") (pinfunction "Q7#_7") (pintype "passive"))
    )
    (net (code "154") (name "unconnected-(U13-Q7#-Pad7)") (class "Default")
      (node (ref "U13") (pin "7") (pinfunction "Q7#_7") (pintype "passive"))
    )
    (net (code "155") (name "unconnected-(U14-Q7#-Pad7)") (class "Default")
      (node (ref "U14") (pin "7") (pinfunction "Q7#_7") (pintype "passive"))
    )
    (net (code "156") (name "unconnected-(U15-DS-Pad10)") (class "Default")
      (node (ref "U15") (pin "10") (pinfunction "DS_10") (pintype "passive"))
    )
    (net (code "157") (name "unconnected-(U15-Q7#-Pad7)") (class "Default")
      (node (ref "U15") (pin "7") (pinfunction "Q7#_7") (pintype "passive"))
    )
    (net (code "158") (name "unconnected-(USB1-SBU1-PadA8)") (class "Default")
      (node (ref "USB1") (pin "A8") (pinfunction "SBU1_A8") (pintype "passive"))
    )
    (net (code "159") (name "unconnected-(USB1-SBU2-PadB8)") (class "Default")
      (node (ref "USB1") (pin "B8") (pinfunction "SBU2_B8") (pintype "passive"))
    )
  )
)
